# Modular_RFPA_v105.net
KiCad netlist of a schematic drawn in EAGLE
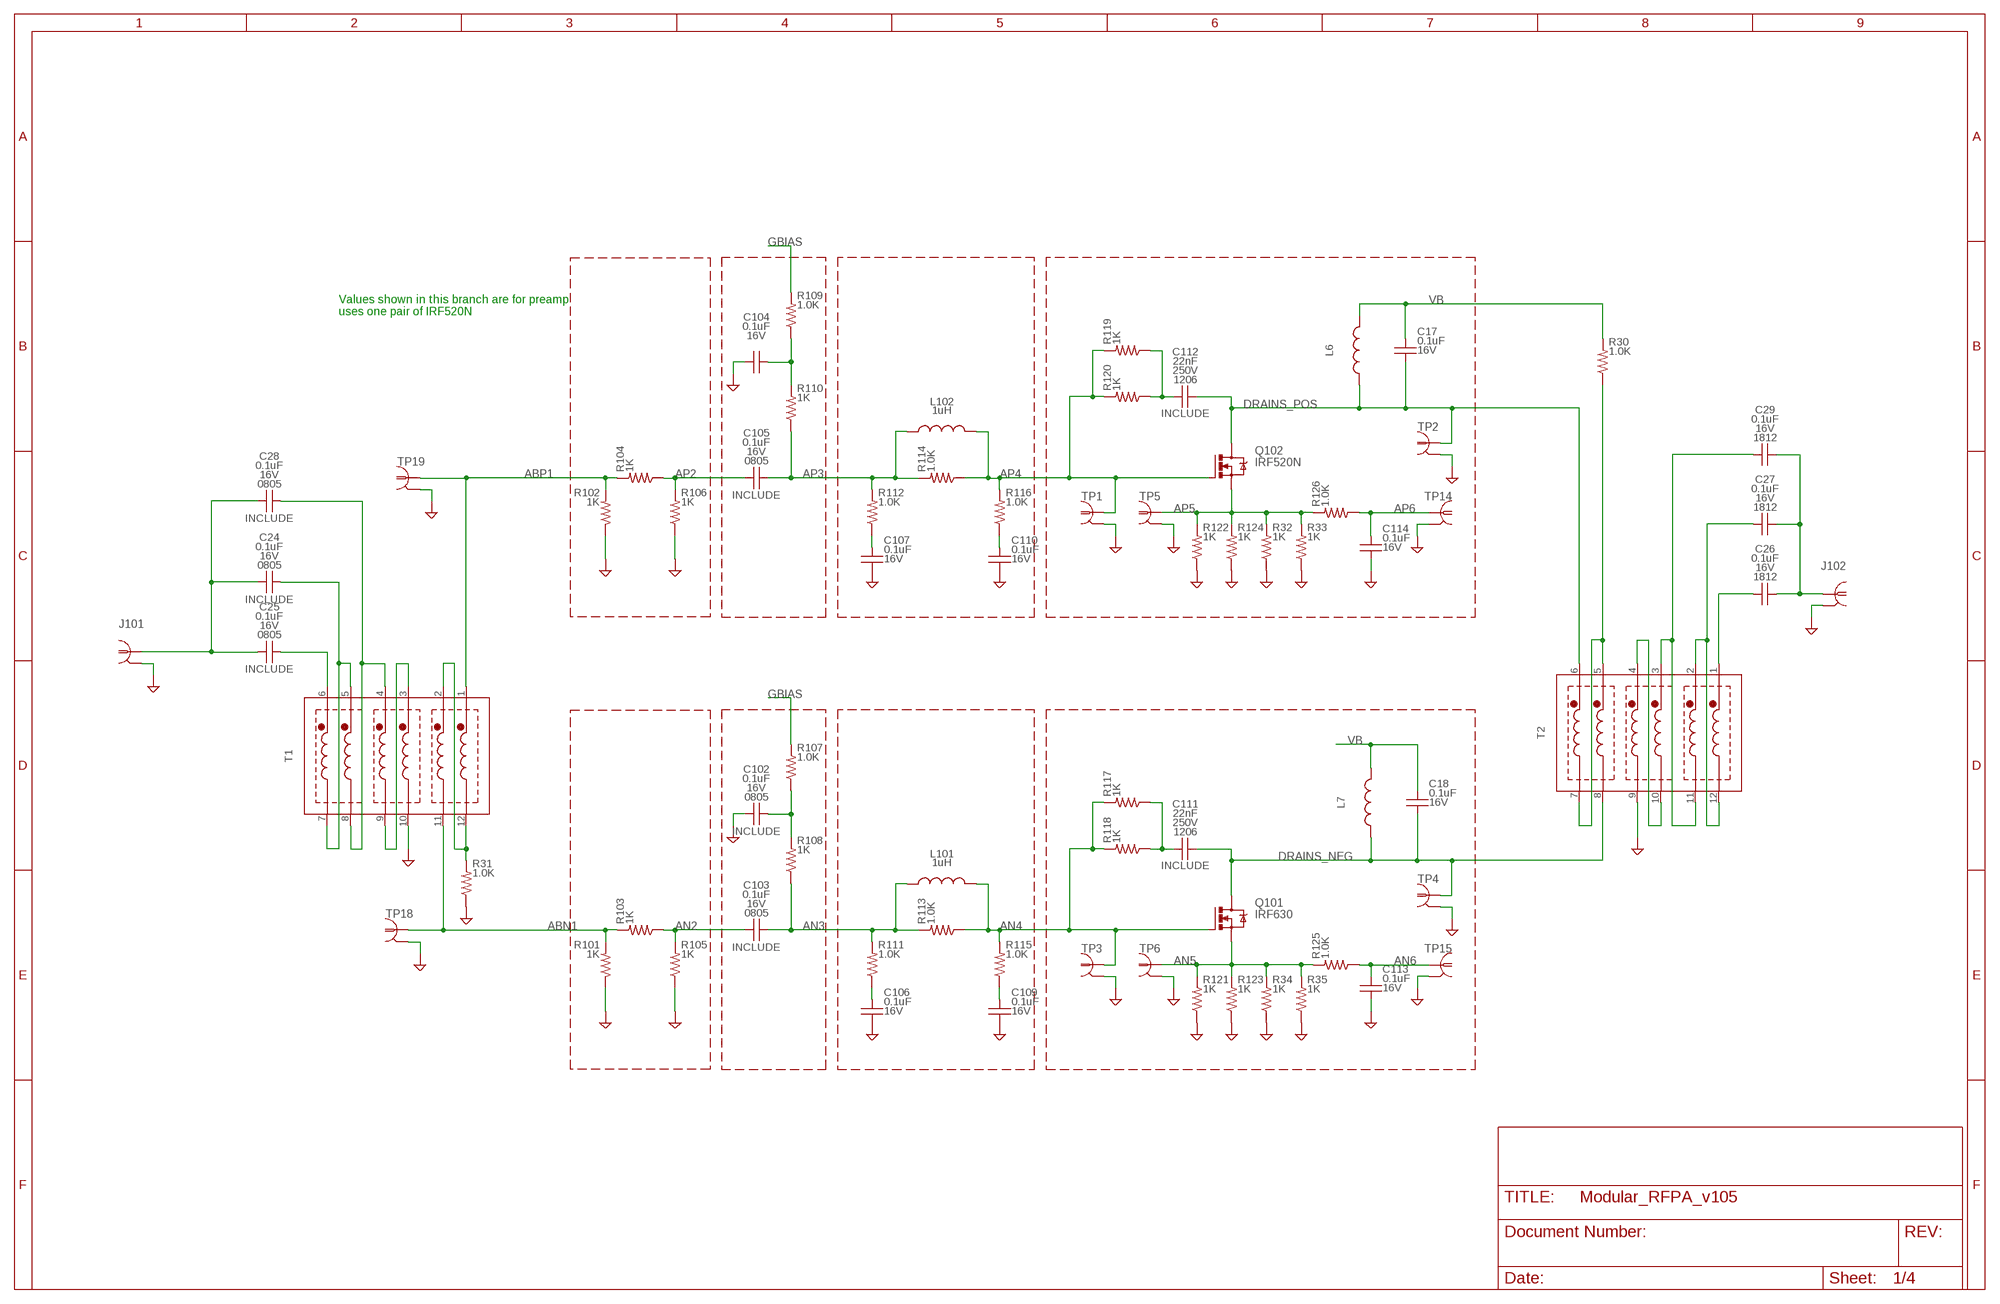
[diagram p0: schematic, sheet 1, part 1 of 2]
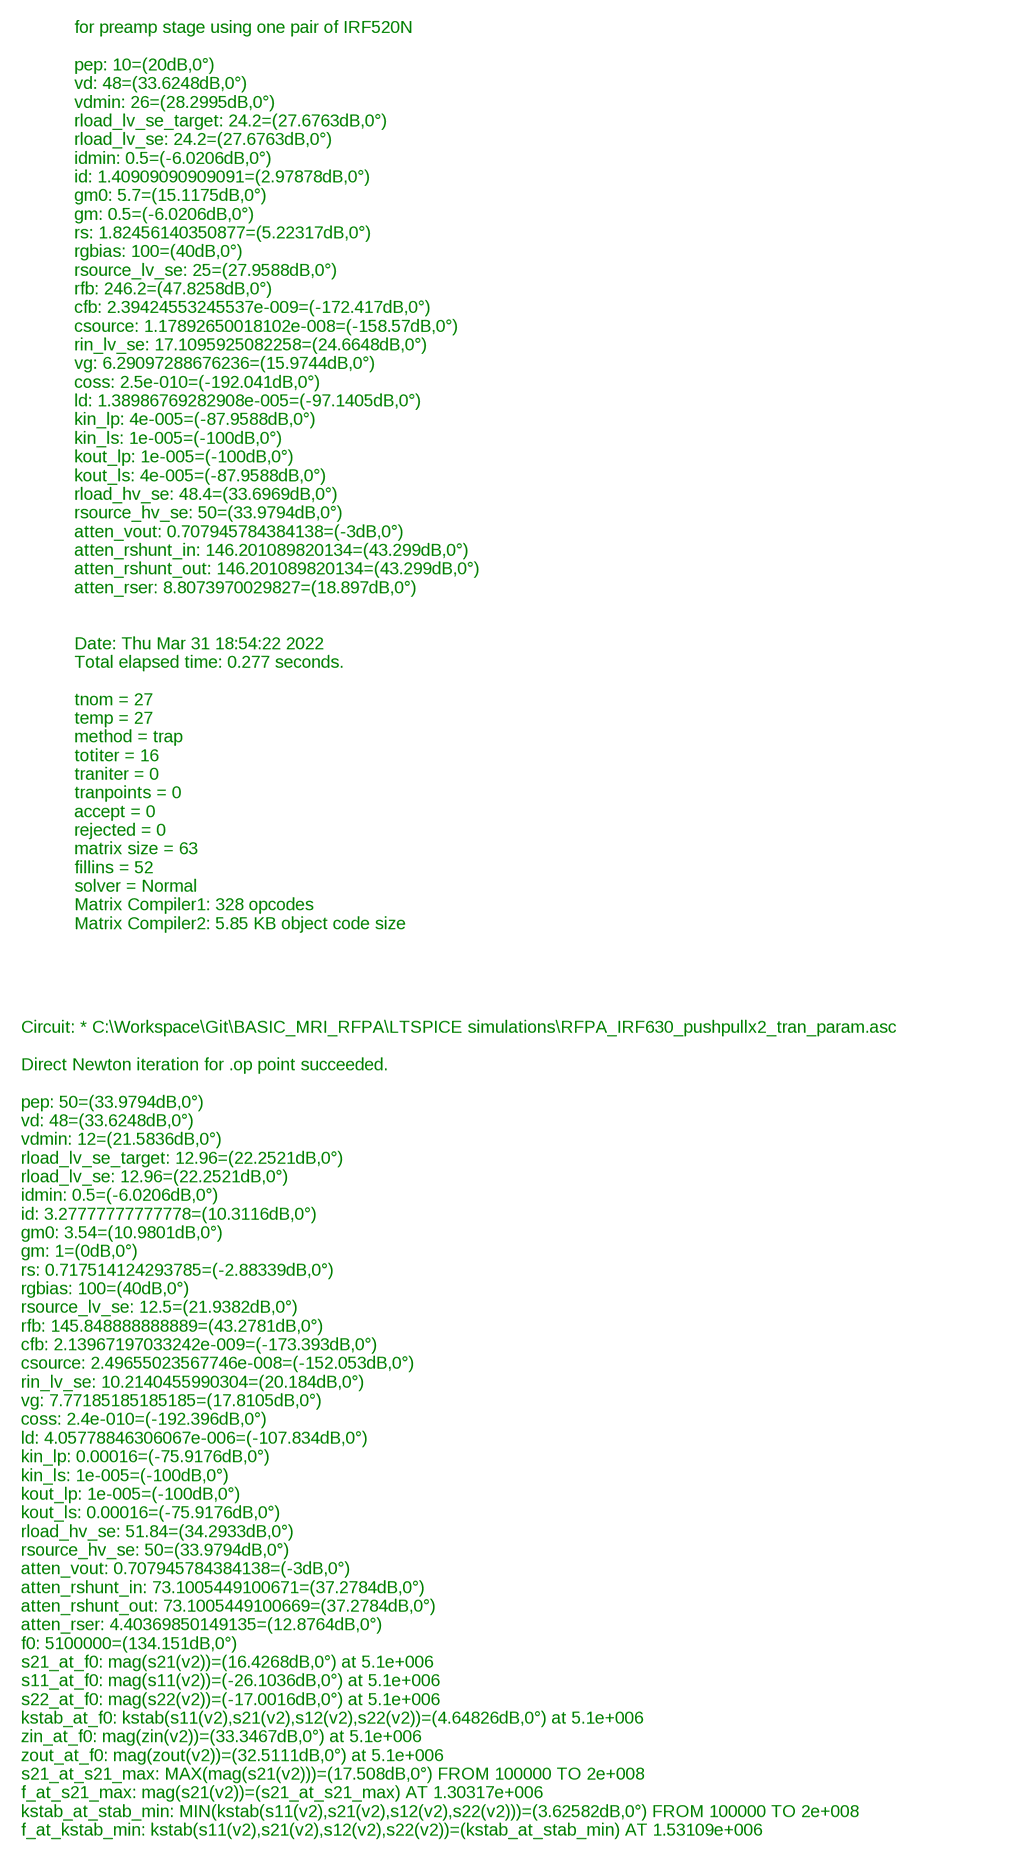
[diagram p1: schematic, sheet 1, part 2 of 2]
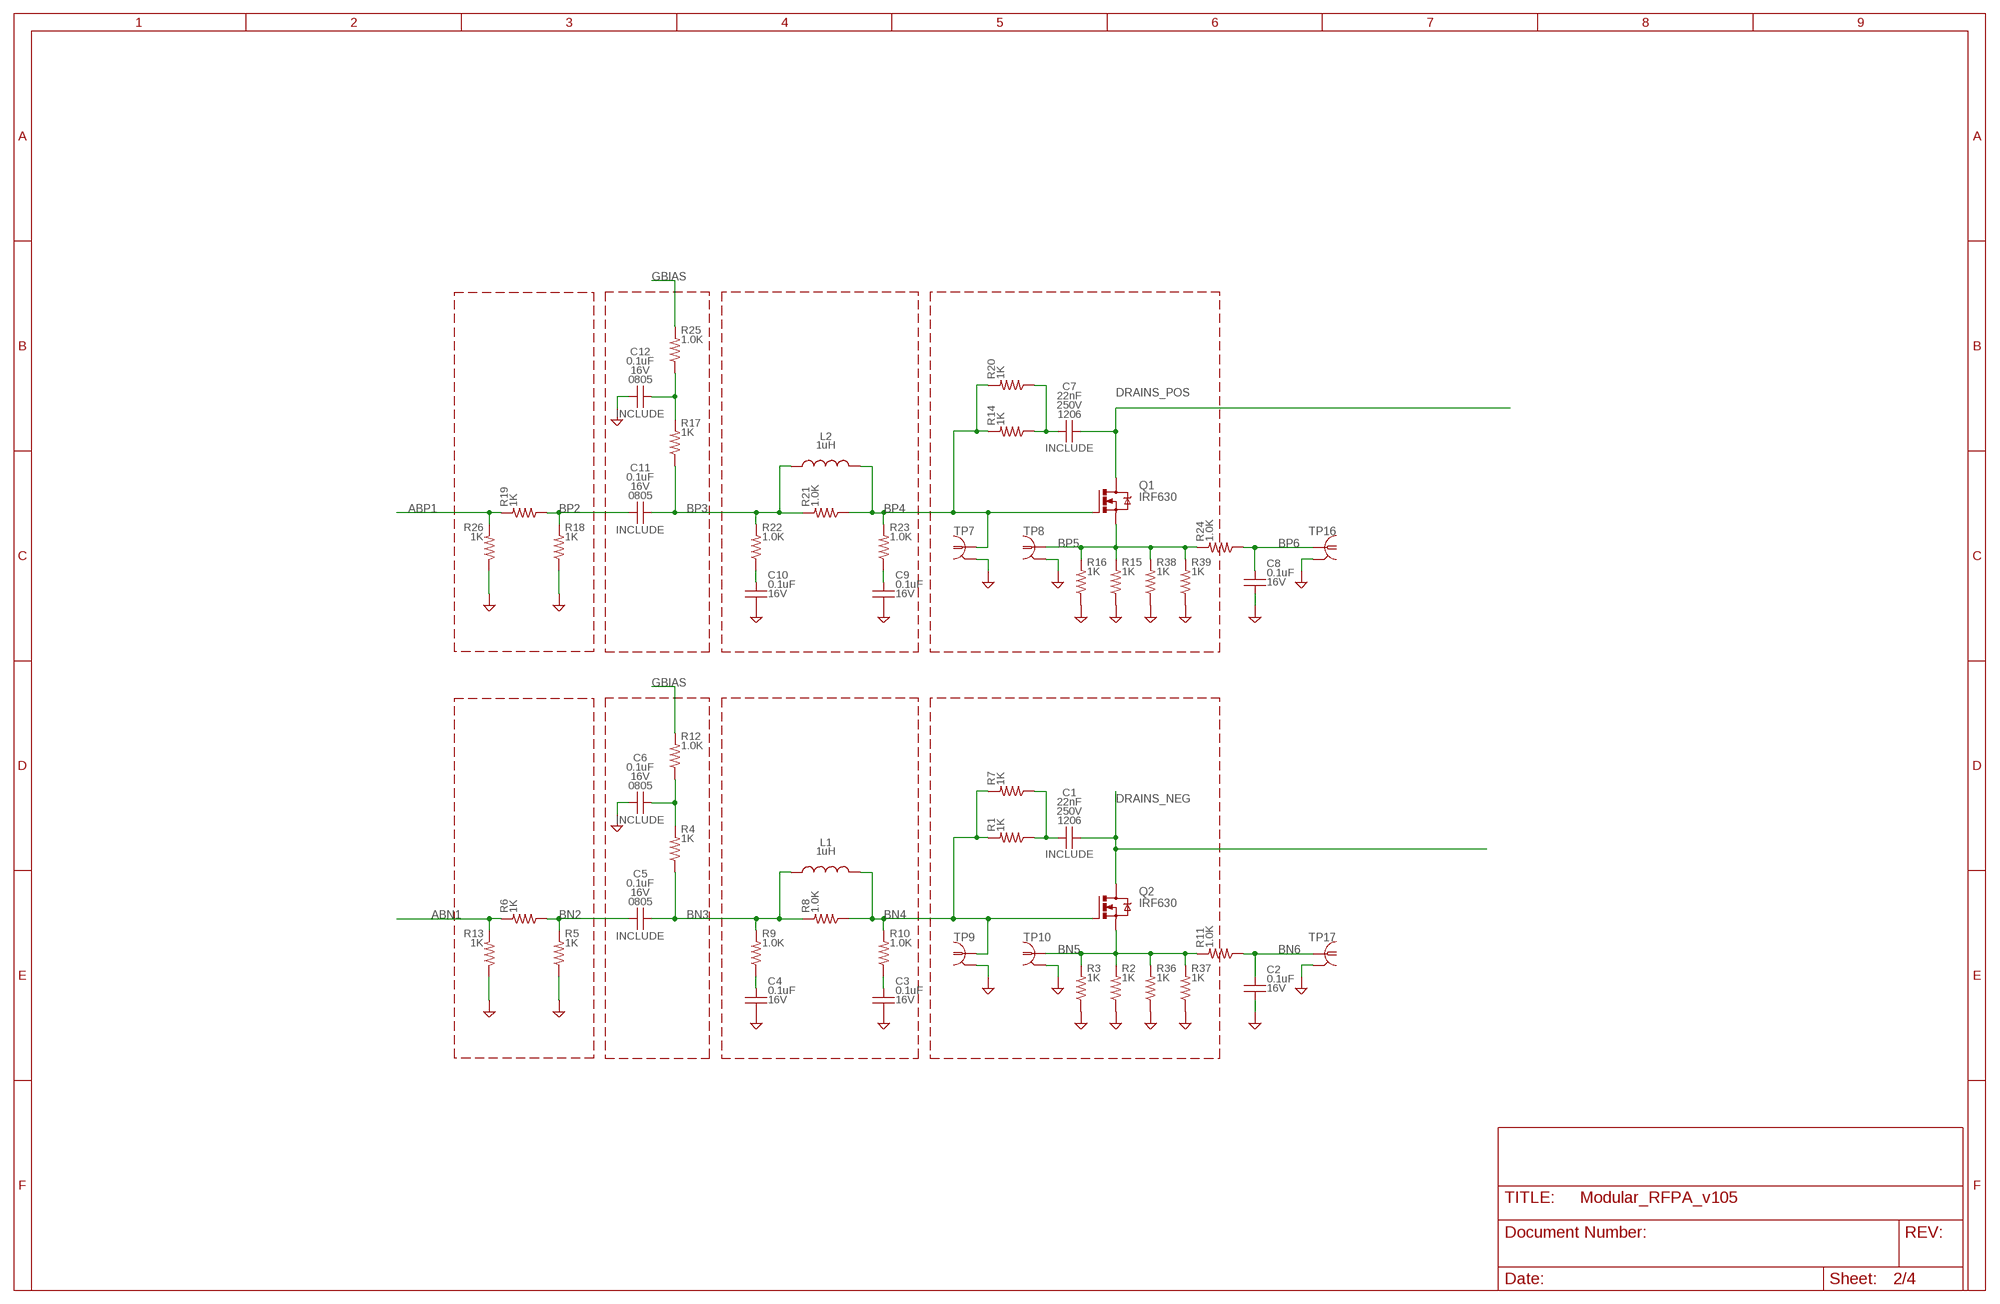
[diagram p2: schematic, sheet 2]
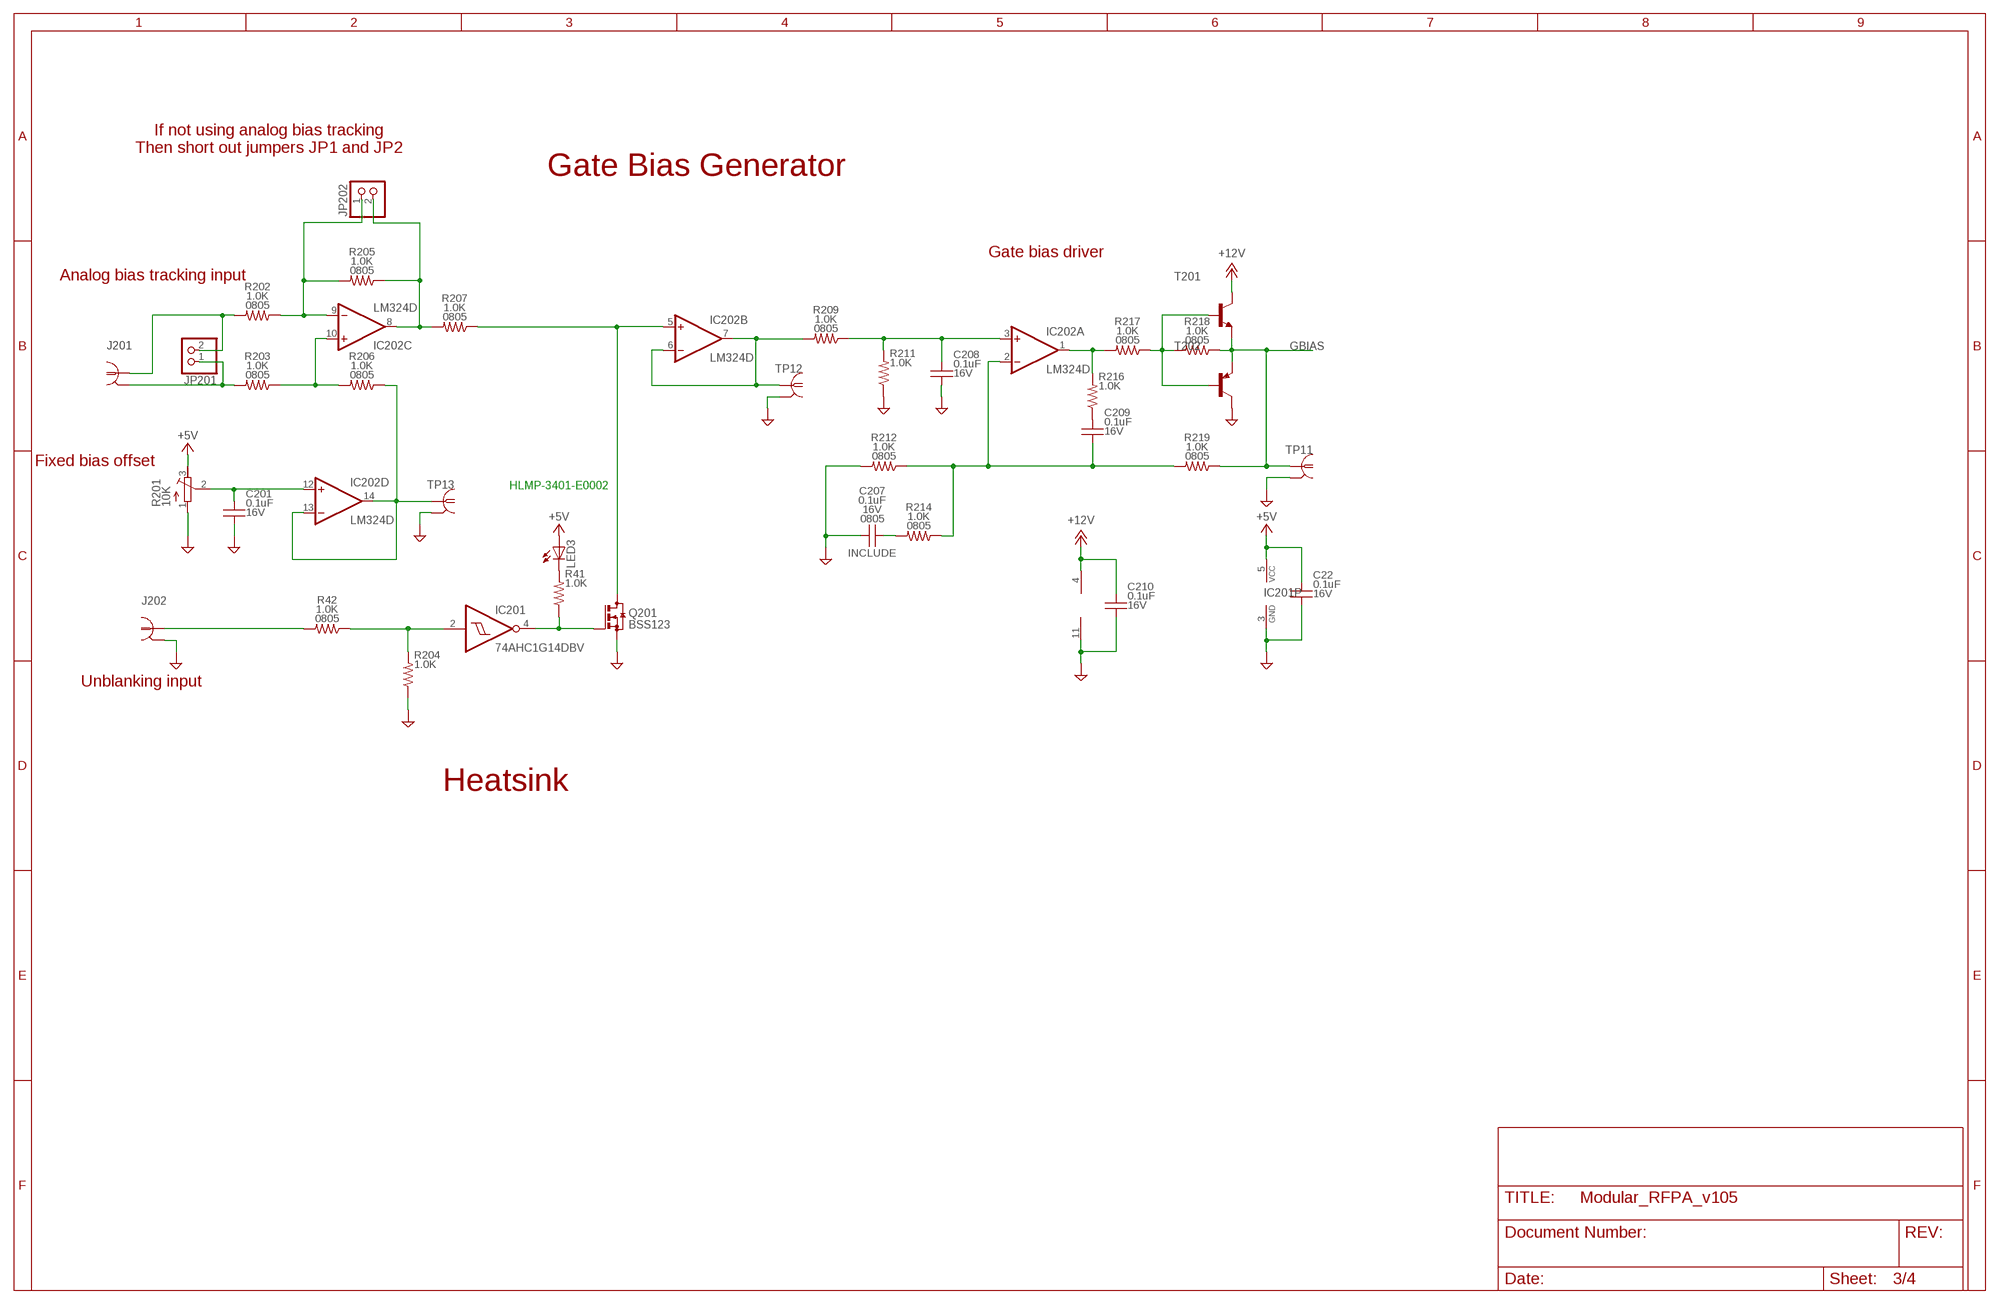
[diagram p3: schematic, sheet 3]
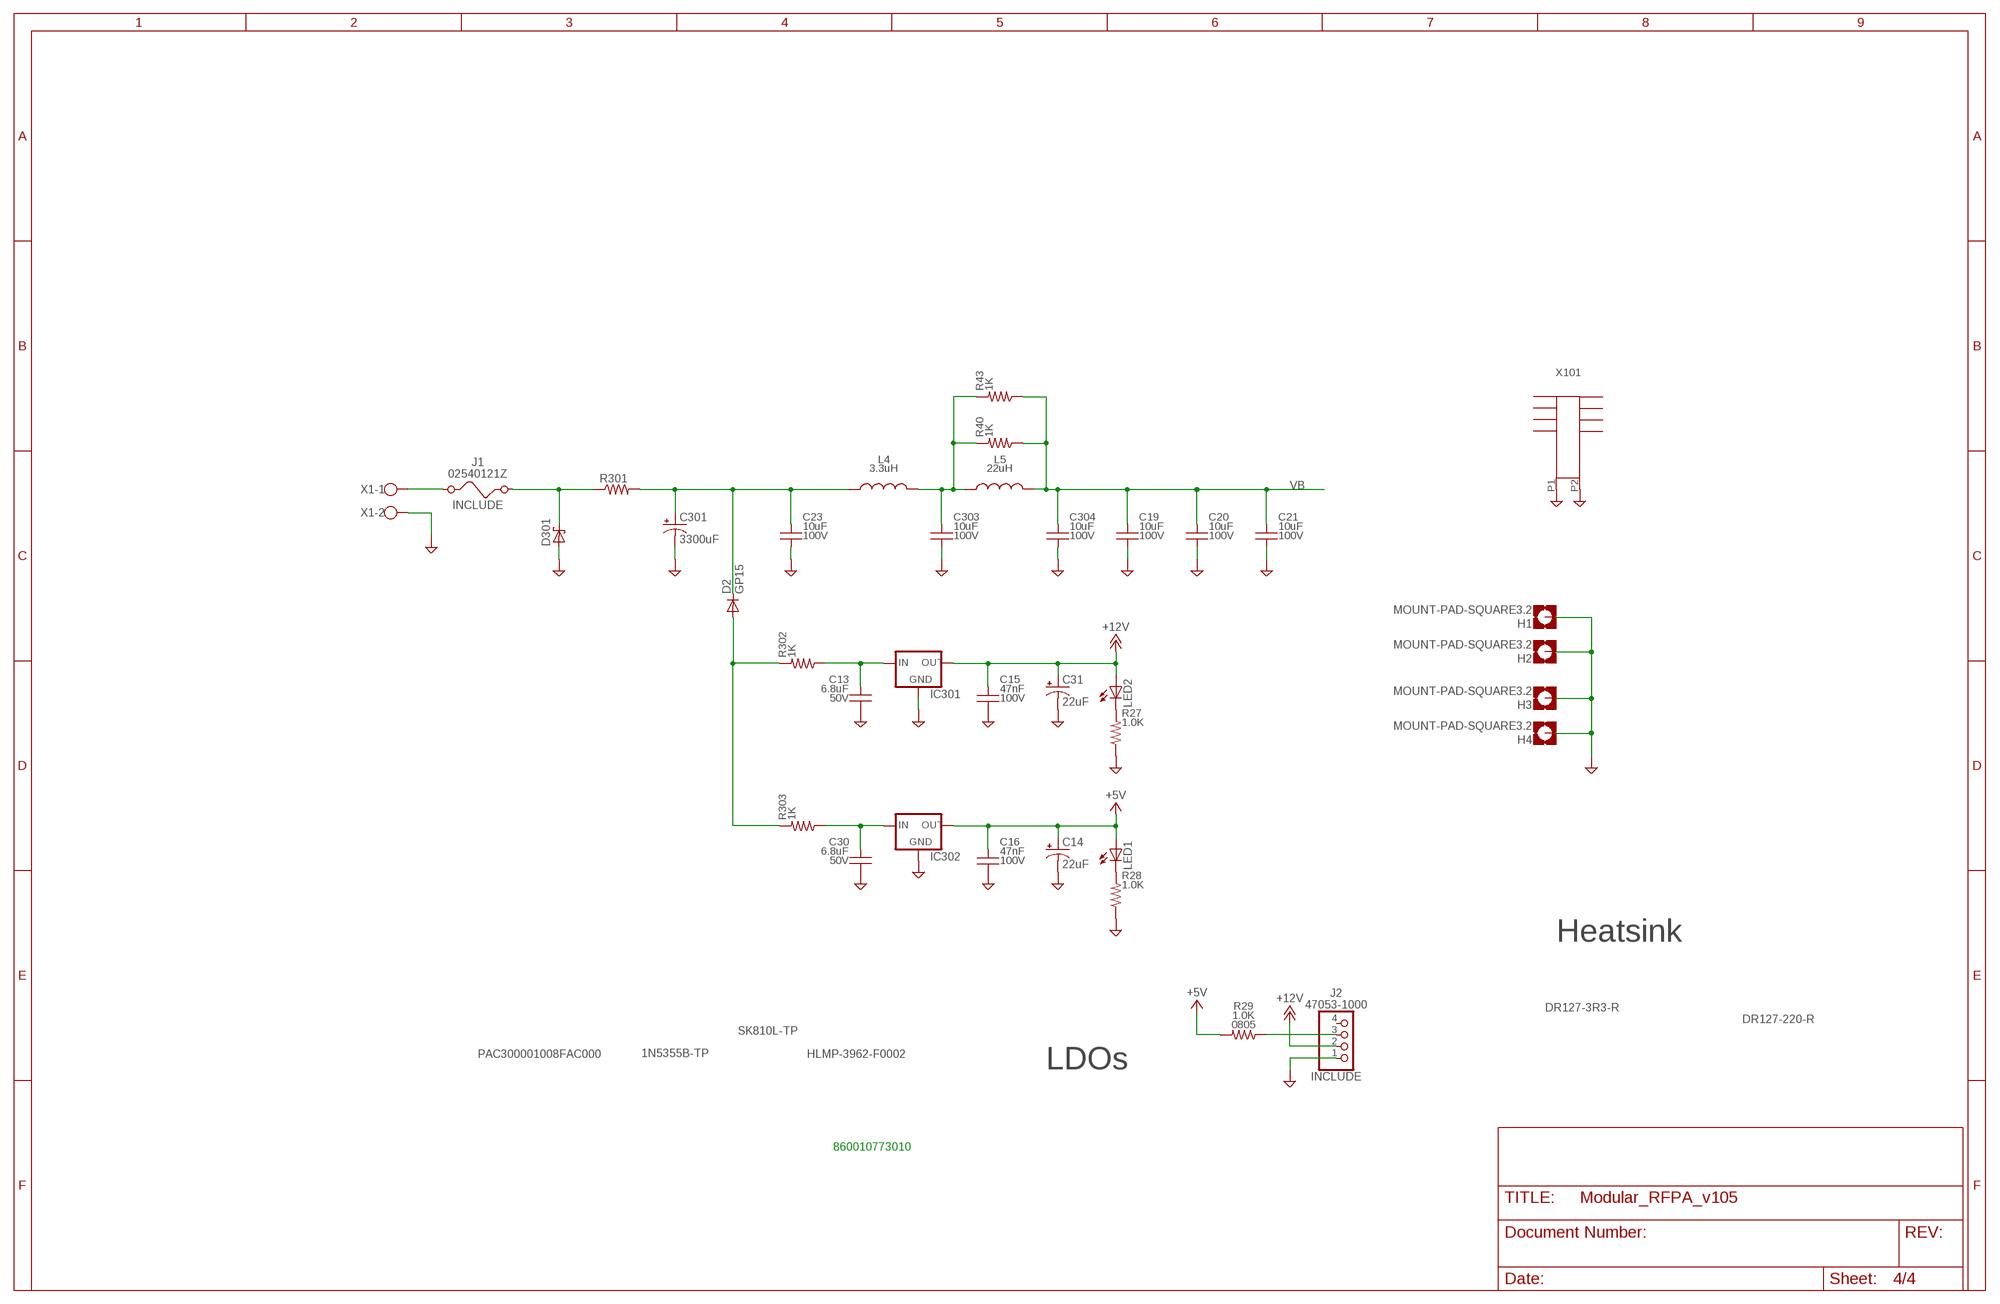
[diagram p4: schematic, sheet 4]

(export (version "E")
  (design (tool "Eeschema 10.0.6"))
  (components
    (comp (ref "C17")
      (value "0.1uF")
      (footprint "eagle-import:C1812")
      (fields (field (name "VOLTAGE") "16V"))
      (libsource (lib "eagle-import") (part "CC1812"))
    )
    (comp (ref "C18")
      (value "0.1uF")
      (footprint "eagle-import:C1812")
      (fields (field (name "VOLTAGE") "16V"))
      (libsource (lib "eagle-import") (part "CC1812"))
    )
    (comp (ref "C24")
      (value "0.1uF")
      (footprint "eagle-import:0805_IPC-7351B")
      (fields (field (name "PACKAGE") "0805") (field (name "VOLTAGE") "16V") (field (name "BOM") "INCLUDE"))
      (libsource (lib "eagle-import") (part "C0805_IPCC-0.1U-16V-0805-X7R"))
    )
    (comp (ref "C25")
      (value "0.1uF")
      (footprint "eagle-import:0805_IPC-7351B")
      (fields (field (name "PACKAGE") "0805") (field (name "VOLTAGE") "16V") (field (name "BOM") "INCLUDE"))
      (libsource (lib "eagle-import") (part "C0805_IPCC-0.1U-16V-0805-X7R"))
    )
    (comp (ref "C26")
      (value "0.1uF")
      (footprint "eagle-import:C1812")
      (fields (field (name "VOLTAGE") "16V") (field (name "PACKAGE") "1812"))
      (libsource (lib "eagle-import") (part "CC1812"))
    )
    (comp (ref "C27")
      (value "0.1uF")
      (footprint "eagle-import:C1812")
      (fields (field (name "VOLTAGE") "16V") (field (name "PACKAGE") "1812"))
      (libsource (lib "eagle-import") (part "CC1812"))
    )
    (comp (ref "C28")
      (value "0.1uF")
      (footprint "eagle-import:0805_IPC-7351B")
      (fields (field (name "PACKAGE") "0805") (field (name "VOLTAGE") "16V") (field (name "BOM") "INCLUDE"))
      (libsource (lib "eagle-import") (part "C0805_IPCC-0.1U-16V-0805-X7R"))
    )
    (comp (ref "C29")
      (value "0.1uF")
      (footprint "eagle-import:C1812")
      (fields (field (name "VOLTAGE") "16V") (field (name "PACKAGE") "1812"))
      (libsource (lib "eagle-import") (part "CC1812"))
    )
    (comp (ref "C102")
      (value "0.1uF")
      (footprint "eagle-import:0805_IPC-7351B")
      (fields (field (name "PACKAGE") "0805") (field (name "VOLTAGE") "16V") (field (name "BOM") "INCLUDE"))
      (libsource (lib "eagle-import") (part "C0805_IPCC-0.1U-16V-0805-X7R"))
    )
    (comp (ref "C103")
      (value "0.1uF")
      (footprint "eagle-import:0805_IPC-7351B")
      (fields (field (name "PACKAGE") "0805") (field (name "VOLTAGE") "16V") (field (name "BOM") "INCLUDE"))
      (libsource (lib "eagle-import") (part "C0805_IPCC-0.1U-16V-0805-X7R"))
    )
    (comp (ref "C104")
      (value "0.1uF")
      (footprint "eagle-import:0805_IPC-7351B")
      (fields (field (name "PACKAGE") "0805") (field (name "VOLTAGE") "16V") (field (name "BOM") "INCLUDE"))
      (libsource (lib "eagle-import") (part "C0805_IPCC-0.1U-16V-0805-X7R"))
    )
    (comp (ref "C105")
      (value "0.1uF")
      (footprint "eagle-import:0805_IPC-7351B")
      (fields (field (name "PACKAGE") "0805") (field (name "VOLTAGE") "16V") (field (name "BOM") "INCLUDE"))
      (libsource (lib "eagle-import") (part "C0805_IPCC-0.1U-16V-0805-X7R"))
    )
    (comp (ref "C106")
      (value "0.1uF")
      (footprint "eagle-import:0805_IPC-7351B")
      (fields (field (name "VOLTAGE") "16V"))
      (libsource (lib "eagle-import") (part "C0805_IPCC-0.1U-16V-0805-X7R"))
    )
    (comp (ref "C107")
      (value "0.1uF")
      (footprint "eagle-import:0805_IPC-7351B")
      (fields (field (name "VOLTAGE") "16V"))
      (libsource (lib "eagle-import") (part "C0805_IPCC-0.1U-16V-0805-X7R"))
    )
    (comp (ref "C109")
      (value "0.1uF")
      (footprint "eagle-import:0805_IPC-7351B")
      (fields (field (name "VOLTAGE") "16V"))
      (libsource (lib "eagle-import") (part "C0805_IPCC-0.1U-16V-0805-X7R"))
    )
    (comp (ref "C110")
      (value "0.1uF")
      (footprint "eagle-import:0805_IPC-7351B")
      (fields (field (name "VOLTAGE") "16V"))
      (libsource (lib "eagle-import") (part "C0805_IPCC-0.1U-16V-0805-X7R"))
    )
    (comp (ref "C111")
      (value "22nF")
      (footprint "eagle-import:C1206")
      (fields
        (field (name "BOM") "INCLUDE")
        (field (name "PACKAGE") "1206")
        (field (name "PARTNO") "C3216NP02E223J160AA")
        (field (name "VOLTAGE") "250V")
      )
      (libsource (lib "eagle-import") (part "CC1206C-22N-250V-5%-1206-NP0"))
    )
    (comp (ref "C112")
      (value "22nF")
      (footprint "eagle-import:C1206")
      (fields
        (field (name "BOM") "INCLUDE")
        (field (name "PACKAGE") "1206")
        (field (name "PARTNO") "C3216NP02E223J160AA")
        (field (name "VOLTAGE") "250V")
      )
      (libsource (lib "eagle-import") (part "CC1206C-22N-250V-5%-1206-NP0"))
    )
    (comp (ref "C113")
      (value "0.1uF")
      (footprint "eagle-import:0805_IPC-7351B")
      (fields (field (name "VOLTAGE") "16V"))
      (libsource (lib "eagle-import") (part "C0805_IPCC-0.1U-16V-0805-X7R"))
    )
    (comp (ref "C114")
      (value "0.1uF")
      (footprint "eagle-import:0805_IPC-7351B")
      (fields (field (name "VOLTAGE") "16V"))
      (libsource (lib "eagle-import") (part "C0805_IPCC-0.1U-16V-0805-X7R"))
    )
    (comp (ref "J101")
      (value "COAXBNC_EDGE")
      (footprint "eagle-import:BNC_EDGE")
      (libsource (lib "eagle-import") (part "COAXBNC_EDGE"))
    )
    (comp (ref "J102")
      (value "COAXBNC_EDGE")
      (footprint "eagle-import:BNC_EDGE")
      (libsource (lib "eagle-import") (part "COAXBNC_EDGE"))
    )
    (comp (ref "L6") (value "L") (footprint "eagle-import:DR127") (libsource (lib "eagle-import") (part "L")))
    (comp (ref "L7") (value "L") (footprint "eagle-import:DR127") (libsource (lib "eagle-import") (part "L")))
    (comp (ref "L101")
      (value "1uH")
      (footprint "eagle-import:L1008")
      (fields (field (name "PARTNO") "1008CS-102XJEC"))
      (libsource (lib "eagle-import") (part "L_CHIP1008L-1.0U-AIR-5%-1008-0.37A"))
    )
    (comp (ref "L102")
      (value "1uH")
      (footprint "eagle-import:L1008")
      (fields (field (name "PARTNO") "1008CS-102XJEC"))
      (libsource (lib "eagle-import") (part "L_CHIP1008L-1.0U-AIR-5%-1008-0.37A"))
    )
    (comp (ref "Q101")
      (value "IRF630")
      (footprint "eagle-import:TO220BV")
      (libsource (lib "eagle-import") (part "IRF540"))
    )
    (comp (ref "Q102")
      (value "IRF520N")
      (footprint "eagle-import:TO220BV")
      (libsource (lib "eagle-import") (part "IRF540"))
    )
    (comp (ref "R30")
      (value "1.0K")
      (footprint "eagle-import:0805_IPC-7351B")
      (libsource (lib "eagle-import") (part "R0805_IPCR-1.0K-0.1%-0805-0.1W"))
    )
    (comp (ref "R31")
      (value "1.0K")
      (footprint "eagle-import:0805_IPC-7351B")
      (libsource (lib "eagle-import") (part "R0805_IPCR-1.0K-0.1%-0805-0.1W"))
    )
    (comp (ref "R32")
      (value "1K")
      (footprint "eagle-import:R2512")
      (fields (field (name "POWER") "1"))
      (libsource (lib "eagle-import") (part "RR2512R-1K-1%-2512-1W"))
    )
    (comp (ref "R33")
      (value "1K")
      (footprint "eagle-import:R2512")
      (fields (field (name "POWER") "1"))
      (libsource (lib "eagle-import") (part "RR2512R-1K-1%-2512-1W"))
    )
    (comp (ref "R34")
      (value "1K")
      (footprint "eagle-import:R2512")
      (fields (field (name "POWER") "1"))
      (libsource (lib "eagle-import") (part "RR2512R-1K-1%-2512-1W"))
    )
    (comp (ref "R35")
      (value "1K")
      (footprint "eagle-import:R2512")
      (fields (field (name "POWER") "1"))
      (libsource (lib "eagle-import") (part "RR2512R-1K-1%-2512-1W"))
    )
    (comp (ref "R101")
      (value "1K")
      (footprint "eagle-import:R1206")
      (fields (field (name "POWER") "0.25"))
      (libsource (lib "eagle-import") (part "RR1206R-1.0K-1%-1206-0.25W"))
    )
    (comp (ref "R102")
      (value "1K")
      (footprint "eagle-import:R1206")
      (fields (field (name "POWER") "0.25"))
      (libsource (lib "eagle-import") (part "RR1206R-1.0K-1%-1206-0.25W"))
    )
    (comp (ref "R103")
      (value "1K")
      (footprint "eagle-import:R1206")
      (fields (field (name "POWER") "0.25"))
      (libsource (lib "eagle-import") (part "RR1206R-1.0K-1%-1206-0.25W"))
    )
    (comp (ref "R104")
      (value "1K")
      (footprint "eagle-import:R1206")
      (fields (field (name "POWER") "0.25"))
      (libsource (lib "eagle-import") (part "RR1206R-1.0K-1%-1206-0.25W"))
    )
    (comp (ref "R105")
      (value "1K")
      (footprint "eagle-import:R1206")
      (fields (field (name "POWER") "0.25"))
      (libsource (lib "eagle-import") (part "RR1206R-1.0K-1%-1206-0.25W"))
    )
    (comp (ref "R106")
      (value "1K")
      (footprint "eagle-import:R1206")
      (fields (field (name "POWER") "0.25"))
      (libsource (lib "eagle-import") (part "RR1206R-1.0K-1%-1206-0.25W"))
    )
    (comp (ref "R107")
      (value "1.0K")
      (footprint "eagle-import:0805_IPC-7351B")
      (libsource (lib "eagle-import") (part "R0805_IPCR-1.0K-0.1%-0805-0.1W"))
    )
    (comp (ref "R108")
      (value "1K")
      (footprint "eagle-import:R1206")
      (fields (field (name "POWER") "0.25"))
      (libsource (lib "eagle-import") (part "RR1206R-1.0K-1%-1206-0.25W"))
    )
    (comp (ref "R109")
      (value "1.0K")
      (footprint "eagle-import:0805_IPC-7351B")
      (libsource (lib "eagle-import") (part "R0805_IPCR-1.0K-0.1%-0805-0.1W"))
    )
    (comp (ref "R110")
      (value "1K")
      (footprint "eagle-import:R1206")
      (fields (field (name "POWER") "0.25"))
      (libsource (lib "eagle-import") (part "RR1206R-1.0K-1%-1206-0.25W"))
    )
    (comp (ref "R111")
      (value "1.0K")
      (footprint "eagle-import:0805_IPC-7351B")
      (libsource (lib "eagle-import") (part "R0805_IPCR-1.0K-0.1%-0805-0.1W"))
    )
    (comp (ref "R112")
      (value "1.0K")
      (footprint "eagle-import:0805_IPC-7351B")
      (libsource (lib "eagle-import") (part "R0805_IPCR-1.0K-0.1%-0805-0.1W"))
    )
    (comp (ref "R113")
      (value "1.0K")
      (footprint "eagle-import:0805_IPC-7351B")
      (libsource (lib "eagle-import") (part "R0805_IPCR-1.0K-0.1%-0805-0.1W"))
    )
    (comp (ref "R114")
      (value "1.0K")
      (footprint "eagle-import:0805_IPC-7351B")
      (libsource (lib "eagle-import") (part "R0805_IPCR-1.0K-0.1%-0805-0.1W"))
    )
    (comp (ref "R115")
      (value "1.0K")
      (footprint "eagle-import:0805_IPC-7351B")
      (libsource (lib "eagle-import") (part "R0805_IPCR-1.0K-0.1%-0805-0.1W"))
    )
    (comp (ref "R116")
      (value "1.0K")
      (footprint "eagle-import:0805_IPC-7351B")
      (libsource (lib "eagle-import") (part "R0805_IPCR-1.0K-0.1%-0805-0.1W"))
    )
    (comp (ref "R117")
      (value "1K")
      (footprint "eagle-import:R2512")
      (fields (field (name "POWER") "1"))
      (libsource (lib "eagle-import") (part "RR2512R-1K-1%-2512-1W"))
    )
    (comp (ref "R118")
      (value "1K")
      (footprint "eagle-import:R2512")
      (fields (field (name "POWER") "1"))
      (libsource (lib "eagle-import") (part "RR2512R-1K-1%-2512-1W"))
    )
    (comp (ref "R119")
      (value "1K")
      (footprint "eagle-import:R2512")
      (fields (field (name "POWER") "1"))
      (libsource (lib "eagle-import") (part "RR2512R-1K-1%-2512-1W"))
    )
    (comp (ref "R120")
      (value "1K")
      (footprint "eagle-import:R2512")
      (fields (field (name "POWER") "1"))
      (libsource (lib "eagle-import") (part "RR2512R-1K-1%-2512-1W"))
    )
    (comp (ref "R121")
      (value "1K")
      (footprint "eagle-import:R2512")
      (fields (field (name "POWER") "1"))
      (libsource (lib "eagle-import") (part "RR2512R-1K-1%-2512-1W"))
    )
    (comp (ref "R122")
      (value "1K")
      (footprint "eagle-import:R2512")
      (fields (field (name "POWER") "1"))
      (libsource (lib "eagle-import") (part "RR2512R-1K-1%-2512-1W"))
    )
    (comp (ref "R123")
      (value "1K")
      (footprint "eagle-import:R2512")
      (fields (field (name "POWER") "1"))
      (libsource (lib "eagle-import") (part "RR2512R-1K-1%-2512-1W"))
    )
    (comp (ref "R124")
      (value "1K")
      (footprint "eagle-import:R2512")
      (fields (field (name "POWER") "1"))
      (libsource (lib "eagle-import") (part "RR2512R-1K-1%-2512-1W"))
    )
    (comp (ref "R125")
      (value "1.0K")
      (footprint "eagle-import:0805_IPC-7351B")
      (libsource (lib "eagle-import") (part "R0805_IPCR-1.0K-0.1%-0805-0.1W"))
    )
    (comp (ref "R126")
      (value "1.0K")
      (footprint "eagle-import:0805_IPC-7351B")
      (fields (field (name "PACKAGE") "0805"))
      (libsource (lib "eagle-import") (part "R0805_IPCR-1.0K-0.1%-0805-0.1W"))
    )
    (comp (ref "T1")
      (value "HP4_TRAFO")
      (footprint "eagle-import:HP4")
      (libsource (lib "eagle-import") (part "HP4_TRAFO"))
    )
    (comp (ref "T2")
      (value "HP4_TRAFO")
      (footprint "eagle-import:HP4")
      (libsource (lib "eagle-import") (part "HP4_TRAFO"))
    )
    (comp (ref "TP1")
      (value "PROBE_TPTP_5MM")
      (footprint "eagle-import:PROBE_TP_5MM")
      (libsource (lib "eagle-import") (part "PROBE_TPTP_5MM"))
    )
    (comp (ref "TP2")
      (value "PROBE_TPTP_7P5MM")
      (footprint "eagle-import:PROBE_TP_7P5MM")
      (libsource (lib "eagle-import") (part "PROBE_TPTP_7P5MM"))
    )
    (comp (ref "TP3")
      (value "PROBE_TPTP_5MM")
      (footprint "eagle-import:PROBE_TP_5MM")
      (libsource (lib "eagle-import") (part "PROBE_TPTP_5MM"))
    )
    (comp (ref "TP4")
      (value "PROBE_TPTP_7P5MM")
      (footprint "eagle-import:PROBE_TP_7P5MM")
      (libsource (lib "eagle-import") (part "PROBE_TPTP_7P5MM"))
    )
    (comp (ref "TP5")
      (value "PROBE_TPTP_7P5MM")
      (footprint "eagle-import:PROBE_TP_7P5MM")
      (libsource (lib "eagle-import") (part "PROBE_TPTP_7P5MM"))
    )
    (comp (ref "TP6")
      (value "PROBE_TPTP_7P5MM")
      (footprint "eagle-import:PROBE_TP_7P5MM")
      (libsource (lib "eagle-import") (part "PROBE_TPTP_7P5MM"))
    )
    (comp (ref "TP14")
      (value "PROBE_TPTP_5MM")
      (footprint "eagle-import:PROBE_TP_5MM")
      (libsource (lib "eagle-import") (part "PROBE_TPTP_5MM"))
    )
    (comp (ref "TP15")
      (value "PROBE_TPTP_5MM")
      (footprint "eagle-import:PROBE_TP_5MM")
      (libsource (lib "eagle-import") (part "PROBE_TPTP_5MM"))
    )
    (comp (ref "TP18")
      (value "PROBE_TPTP_5MM")
      (footprint "eagle-import:PROBE_TP_5MM")
      (libsource (lib "eagle-import") (part "PROBE_TPTP_5MM"))
    )
    (comp (ref "TP19")
      (value "PROBE_TPTP_5MM")
      (footprint "eagle-import:PROBE_TP_5MM")
      (libsource (lib "eagle-import") (part "PROBE_TPTP_5MM"))
    )
    (comp (ref "C13")
      (value "6.8uF")
      (footprint "eagle-import:C1210")
      (fields (field (name "PARTNO") "CGA6P3X7S1H685K250AB") (field (name "VOLTAGE") "50V"))
      (libsource (lib "eagle-import") (part "CC1210CC-6.8U-50V-10%-1210-X7S"))
    )
    (comp (ref "C14")
      (value "22uF")
      (footprint "eagle-import:E2,5-7")
      (libsource (lib "eagle-import") (part "CPOL-USE2.5-7"))
    )
    (comp (ref "C15")
      (value "47nF")
      (footprint "eagle-import:C1206")
      (fields (field (name "PARTNO") "C3216C0G2A473J115AC") (field (name "VOLTAGE") "100V"))
      (libsource (lib "eagle-import") (part "CC1206C-47N-100V-5%-1206-NP0"))
    )
    (comp (ref "C16")
      (value "47nF")
      (footprint "eagle-import:C1206")
      (fields (field (name "PARTNO") "C3216C0G2A473J115AC") (field (name "VOLTAGE") "100V"))
      (libsource (lib "eagle-import") (part "CC1206C-47N-100V-5%-1206-NP0"))
    )
    (comp (ref "C19")
      (value "10uF")
      (footprint "eagle-import:C2220_CKG57N")
      (fields (field (name "PARTNO") "CGA9N3X7S2A106M230KE") (field (name "VOLTAGE") "100V"))
      (libsource (lib "eagle-import") (part "CC2220_CKG57NCC-10U-100V-20%-2220-X7T"))
    )
    (comp (ref "C20")
      (value "10uF")
      (footprint "eagle-import:C2220_CKG57N")
      (fields (field (name "PARTNO") "CGA9N3X7S2A106M230KE") (field (name "VOLTAGE") "100V"))
      (libsource (lib "eagle-import") (part "CC2220_CKG57NCC-10U-100V-20%-2220-X7T"))
    )
    (comp (ref "C21")
      (value "10uF")
      (footprint "eagle-import:C2220_CKG57N")
      (fields (field (name "PARTNO") "CGA9N3X7S2A106M230KE") (field (name "VOLTAGE") "100V"))
      (libsource (lib "eagle-import") (part "CC2220_CKG57NCC-10U-100V-20%-2220-X7T"))
    )
    (comp (ref "C23")
      (value "10uF")
      (footprint "eagle-import:C2220_CKG57N")
      (fields
        (field (name "BOM") "INCLUDE")
        (field (name "PACKAGE") "2220")
        (field (name "PARTNO") "CGA9N3X7S2A106M230KE")
        (field (name "VOLTAGE") "100V")
      )
      (libsource (lib "eagle-import") (part "CC2220_CKG57NCC-10U-100V-20%-2220-X7T"))
    )
    (comp (ref "C30")
      (value "6.8uF")
      (footprint "eagle-import:C1210")
      (fields (field (name "PARTNO") "CGA6P3X7S1H685K250AB") (field (name "VOLTAGE") "50V"))
      (libsource (lib "eagle-import") (part "CC1210CC-6.8U-50V-10%-1210-X7S"))
    )
    (comp (ref "C31")
      (value "22uF")
      (footprint "eagle-import:E2,5-7")
      (libsource (lib "eagle-import") (part "CPOL-USE2.5-7"))
    )
    (comp (ref "C301")
      (value "3300uF")
      (footprint "eagle-import:EB25D")
      (libsource (lib "eagle-import") (part "CPOL-USE10-25"))
    )
    (comp (ref "C303")
      (value "10uF")
      (footprint "eagle-import:C2220_CKG57N")
      (fields
        (field (name "BOM") "INCLUDE")
        (field (name "PACKAGE") "2220")
        (field (name "PARTNO") "CGA9N3X7S2A106M230KE")
        (field (name "VOLTAGE") "100V")
      )
      (libsource (lib "eagle-import") (part "CC2220_CKG57NCC-10U-100V-20%-2220-X7T"))
    )
    (comp (ref "C304")
      (value "10uF")
      (footprint "eagle-import:C2220_CKG57N")
      (fields (field (name "PARTNO") "CGA9N3X7S2A106M230KE") (field (name "VOLTAGE") "100V"))
      (libsource (lib "eagle-import") (part "CC2220_CKG57NCC-10U-100V-20%-2220-X7T"))
    )
    (comp (ref "D2")
      (value "GP15")
      (footprint "eagle-import:DO15-12")
      (libsource (lib "eagle-import") (part "GP15"))
    )
    (comp (ref "D301")
      (value "SCHOTTKY-DIODESMC")
      (footprint "eagle-import:SMC")
      (libsource (lib "eagle-import") (part "SCHOTTKY-DIODESMC"))
    )
    (comp (ref "H1")
      (value "MOUNT-PAD-SQUARE3.2")
      (footprint "eagle-import:3,2-PAD-SQUARE")
      (libsource (lib "eagle-import") (part "MOUNT-PAD-SQUARE3.2"))
    )
    (comp (ref "H2")
      (value "MOUNT-PAD-SQUARE3.2")
      (footprint "eagle-import:3,2-PAD-SQUARE")
      (libsource (lib "eagle-import") (part "MOUNT-PAD-SQUARE3.2"))
    )
    (comp (ref "H3")
      (value "MOUNT-PAD-SQUARE3.2")
      (footprint "eagle-import:3,2-PAD-SQUARE")
      (libsource (lib "eagle-import") (part "MOUNT-PAD-SQUARE3.2"))
    )
    (comp (ref "H4")
      (value "MOUNT-PAD-SQUARE3.2")
      (footprint "eagle-import:3,2-PAD-SQUARE")
      (libsource (lib "eagle-import") (part "MOUNT-PAD-SQUARE3.2"))
    )
    (comp (ref "IC301")
      (value "78XXS")
      (footprint "eagle-import:78XXS")
      (libsource (lib "eagle-import") (part "78XXS"))
    )
    (comp (ref "IC302")
      (value "78XXS")
      (footprint "eagle-import:78XXS")
      (libsource (lib "eagle-import") (part "78XXS"))
    )
    (comp (ref "J1")
      (value "FUSE_2P")
      (footprint "eagle-import:02540121Z")
      (fields (field (name "PARTNO") "02540121Z"))
      (libsource (lib "eagle-import") (part "FUSE_2P"))
    )
    (comp (ref "J2")
      (value "KK_PCFAN")
      (footprint "eagle-import:47053-1000")
      (fields (field (name "PARTNO") "47053-1000"))
      (libsource (lib "eagle-import") (part "KK_PCFAN"))
    )
    (comp (ref "L4")
      (value "3.3uH")
      (footprint "eagle-import:DR127")
      (libsource (lib "eagle-import") (part "L"))
    )
    (comp (ref "L5")
      (value "22uH")
      (footprint "eagle-import:DR127")
      (libsource (lib "eagle-import") (part "L"))
    )
    (comp (ref "LED1")
      (value "LED5MM")
      (footprint "eagle-import:LED5MM")
      (libsource (lib "eagle-import") (part "LED5MM"))
    )
    (comp (ref "LED2")
      (value "LED5MM")
      (footprint "eagle-import:LED5MM")
      (libsource (lib "eagle-import") (part "LED5MM"))
    )
    (comp (ref "R27")
      (value "1.0K")
      (footprint "eagle-import:0805_IPC-7351B")
      (libsource (lib "eagle-import") (part "R0805_IPCR-1.0K-0.1%-0805-0.1W"))
    )
    (comp (ref "R28")
      (value "1.0K")
      (footprint "eagle-import:0805_IPC-7351B")
      (libsource (lib "eagle-import") (part "R0805_IPCR-1.0K-0.1%-0805-0.1W"))
    )
    (comp (ref "R29")
      (value "1.0K")
      (footprint "eagle-import:0805_IPC-7351B")
      (fields (field (name "PACKAGE") "0805"))
      (libsource (lib "eagle-import") (part "R0805_IPCR-1.0K-0.1%-0805-0.1W"))
    )
    (comp (ref "R40")
      (value "1K")
      (footprint "eagle-import:R1206")
      (fields (field (name "POWER") "0.25"))
      (libsource (lib "eagle-import") (part "RR1206R-1.0K-1%-1206-0.25W"))
    )
    (comp (ref "R43")
      (value "1K")
      (footprint "eagle-import:R1206")
      (fields (field (name "POWER") "0.25"))
      (libsource (lib "eagle-import") (part "RR1206R-1.0K-1%-1206-0.25W"))
    )
    (comp (ref "R301")
      (value "R-US_0817/7V")
      (footprint "eagle-import:P0817V")
      (libsource (lib "eagle-import") (part "R-US_0817/7V"))
    )
    (comp (ref "R302")
      (value "1K")
      (footprint "eagle-import:R1206")
      (fields (field (name "POWER") "0.25"))
      (libsource (lib "eagle-import") (part "RR1206R-1.0K-1%-1206-0.25W"))
    )
    (comp (ref "R303")
      (value "1K")
      (footprint "eagle-import:R1206")
      (fields (field (name "POWER") "0.25"))
      (libsource (lib "eagle-import") (part "RR1206R-1.0K-1%-1206-0.25W"))
    )
    (comp (ref "X1")
      (value "W237-102")
      (footprint "eagle-import:W237-102")
      (fields (field (name "MPN") "237-102"))
      (libsource (lib "eagle-import") (part "W237-102"))
    )
    (comp (ref "X101")
      (value "HEATSINK_OMNI_DUAL30-75-D")
      (footprint "eagle-import:OMNI-UNI-30-75-D")
      (libsource (lib "eagle-import") (part "HEATSINK_OMNI_DUAL30-75-D"))
    )
    (comp (ref "C22")
      (value "0.1uF")
      (footprint "eagle-import:0805_IPC-7351B")
      (fields (field (name "VOLTAGE") "16V"))
      (libsource (lib "eagle-import") (part "C0805_IPCC-0.1U-16V-0805-X7R"))
    )
    (comp (ref "C201")
      (value "0.1uF")
      (footprint "eagle-import:0805_IPC-7351B")
      (fields (field (name "VOLTAGE") "16V"))
      (libsource (lib "eagle-import") (part "C0805_IPCC-0.1U-16V-0805-X7R"))
    )
    (comp (ref "C207")
      (value "0.1uF")
      (footprint "eagle-import:0805_IPC-7351B")
      (fields (field (name "PACKAGE") "0805") (field (name "VOLTAGE") "16V") (field (name "BOM") "INCLUDE"))
      (libsource (lib "eagle-import") (part "C0805_IPCC-0.1U-16V-0805-X7R"))
    )
    (comp (ref "C208")
      (value "0.1uF")
      (footprint "eagle-import:0805_IPC-7351B")
      (fields (field (name "VOLTAGE") "16V"))
      (libsource (lib "eagle-import") (part "C0805_IPCC-0.1U-16V-0805-X7R"))
    )
    (comp (ref "C209")
      (value "0.1uF")
      (footprint "eagle-import:0805_IPC-7351B")
      (fields (field (name "VOLTAGE") "16V"))
      (libsource (lib "eagle-import") (part "C0805_IPCC-0.1U-16V-0805-X7R"))
    )
    (comp (ref "C210")
      (value "0.1uF")
      (footprint "eagle-import:0805_IPC-7351B")
      (fields (field (name "VOLTAGE") "16V"))
      (libsource (lib "eagle-import") (part "C0805_IPCC-0.1U-16V-0805-X7R"))
    )
    (comp (ref "IC201")
      (value "74AHC1G14DBV")
      (footprint "eagle-import:SOT23-5")
      (libsource (lib "eagle-import") (part "741G14DBVAHC"))
    )
    (comp (ref "IC202")
      (value "LM324D")
      (footprint "eagle-import:SO14")
      (libsource (lib "eagle-import") (part "LM324D"))
    )
    (comp (ref "J201")
      (value "COAXBNC_EDGE")
      (footprint "eagle-import:BNC_EDGE")
      (libsource (lib "eagle-import") (part "COAXBNC_EDGE"))
    )
    (comp (ref "J202")
      (value "COAXBNC_EDGE")
      (footprint "eagle-import:BNC_EDGE")
      (libsource (lib "eagle-import") (part "COAXBNC_EDGE"))
    )
    (comp (ref "JP201")
      (value "PINHD-1X2")
      (footprint "eagle-import:1X02")
      (libsource (lib "eagle-import") (part "PINHD-1X2"))
    )
    (comp (ref "JP202")
      (value "PINHD-1X2")
      (footprint "eagle-import:1X02")
      (libsource (lib "eagle-import") (part "PINHD-1X2"))
    )
    (comp (ref "LED3")
      (value "LED5MM")
      (footprint "eagle-import:LED5MM")
      (libsource (lib "eagle-import") (part "LED5MM"))
    )
    (comp (ref "Q201")
      (value "BSS123")
      (footprint "eagle-import:SOT23")
      (libsource (lib "eagle-import") (part "BSS123"))
    )
    (comp (ref "R41")
      (value "1.0K")
      (footprint "eagle-import:0805_IPC-7351B")
      (libsource (lib "eagle-import") (part "R0805_IPCR-1.0K-0.1%-0805-0.1W"))
    )
    (comp (ref "R42")
      (value "1.0K")
      (footprint "eagle-import:0805_IPC-7351B")
      (fields (field (name "PACKAGE") "0805"))
      (libsource (lib "eagle-import") (part "R0805_IPCR-1.0K-0.1%-0805-0.1W"))
    )
    (comp (ref "R201")
      (value "10K")
      (footprint "eagle-import:RTRIM3299W")
      (libsource (lib "eagle-import") (part "R-TRIMM3299W"))
    )
    (comp (ref "R202")
      (value "1.0K")
      (footprint "eagle-import:0805_IPC-7351B")
      (fields (field (name "PACKAGE") "0805"))
      (libsource (lib "eagle-import") (part "R0805_IPCR-1.0K-0.1%-0805-0.1W"))
    )
    (comp (ref "R203")
      (value "1.0K")
      (footprint "eagle-import:0805_IPC-7351B")
      (fields (field (name "PACKAGE") "0805"))
      (libsource (lib "eagle-import") (part "R0805_IPCR-1.0K-0.1%-0805-0.1W"))
    )
    (comp (ref "R204")
      (value "1.0K")
      (footprint "eagle-import:0805_IPC-7351B")
      (libsource (lib "eagle-import") (part "R0805_IPCR-1.0K-0.1%-0805-0.1W"))
    )
    (comp (ref "R205")
      (value "1.0K")
      (footprint "eagle-import:0805_IPC-7351B")
      (fields (field (name "PACKAGE") "0805"))
      (libsource (lib "eagle-import") (part "R0805_IPCR-1.0K-0.1%-0805-0.1W"))
    )
    (comp (ref "R206")
      (value "1.0K")
      (footprint "eagle-import:0805_IPC-7351B")
      (fields (field (name "PACKAGE") "0805"))
      (libsource (lib "eagle-import") (part "R0805_IPCR-1.0K-0.1%-0805-0.1W"))
    )
    (comp (ref "R207")
      (value "1.0K")
      (footprint "eagle-import:0805_IPC-7351B")
      (fields (field (name "PACKAGE") "0805"))
      (libsource (lib "eagle-import") (part "R0805_IPCR-1.0K-0.1%-0805-0.1W"))
    )
    (comp (ref "R209")
      (value "1.0K")
      (footprint "eagle-import:0805_IPC-7351B")
      (fields (field (name "PACKAGE") "0805"))
      (libsource (lib "eagle-import") (part "R0805_IPCR-1.0K-0.1%-0805-0.1W"))
    )
    (comp (ref "R211")
      (value "1.0K")
      (footprint "eagle-import:0805_IPC-7351B")
      (libsource (lib "eagle-import") (part "R0805_IPCR-1.0K-0.1%-0805-0.1W"))
    )
    (comp (ref "R212")
      (value "1.0K")
      (footprint "eagle-import:0805_IPC-7351B")
      (fields (field (name "PACKAGE") "0805"))
      (libsource (lib "eagle-import") (part "R0805_IPCR-1.0K-0.1%-0805-0.1W"))
    )
    (comp (ref "R214")
      (value "1.0K")
      (footprint "eagle-import:0805_IPC-7351B")
      (fields (field (name "PACKAGE") "0805"))
      (libsource (lib "eagle-import") (part "R0805_IPCR-1.0K-0.1%-0805-0.1W"))
    )
    (comp (ref "R216")
      (value "1.0K")
      (footprint "eagle-import:0805_IPC-7351B")
      (libsource (lib "eagle-import") (part "R0805_IPCR-1.0K-0.1%-0805-0.1W"))
    )
    (comp (ref "R217")
      (value "1.0K")
      (footprint "eagle-import:0805_IPC-7351B")
      (fields (field (name "PACKAGE") "0805"))
      (libsource (lib "eagle-import") (part "R0805_IPCR-1.0K-0.1%-0805-0.1W"))
    )
    (comp (ref "R218")
      (value "1.0K")
      (footprint "eagle-import:0805_IPC-7351B")
      (fields (field (name "PACKAGE") "0805"))
      (libsource (lib "eagle-import") (part "R0805_IPCR-1.0K-0.1%-0805-0.1W"))
    )
    (comp (ref "R219")
      (value "1.0K")
      (footprint "eagle-import:0805_IPC-7351B")
      (fields (field (name "PACKAGE") "0805"))
      (libsource (lib "eagle-import") (part "R0805_IPCR-1.0K-0.1%-0805-0.1W"))
    )
    (comp (ref "T201")
      (value "BC808-NPN-SOT23-BEC")
      (footprint "eagle-import:SOT23-BEC")
      (libsource (lib "eagle-import") (part "-NPN-SOT23-BECBC808"))
    )
    (comp (ref "T202")
      (value "BC807-16-PNP-SOT23-BEC")
      (footprint "eagle-import:SOT23-BEC")
      (libsource (lib "eagle-import") (part "-PNP-SOT23-BECBC807-16"))
    )
    (comp (ref "TP11")
      (value "PROBE_TPTP_5MM")
      (footprint "eagle-import:PROBE_TP_5MM")
      (libsource (lib "eagle-import") (part "PROBE_TPTP_5MM"))
    )
    (comp (ref "TP12")
      (value "PROBE_TPTP_5MM")
      (footprint "eagle-import:PROBE_TP_5MM")
      (libsource (lib "eagle-import") (part "PROBE_TPTP_5MM"))
    )
    (comp (ref "TP13")
      (value "PROBE_TPTP_5MM")
      (footprint "eagle-import:PROBE_TP_5MM")
      (libsource (lib "eagle-import") (part "PROBE_TPTP_5MM"))
    )
    (comp (ref "C1")
      (value "22nF")
      (footprint "eagle-import:C1206")
      (fields
        (field (name "BOM") "INCLUDE")
        (field (name "PACKAGE") "1206")
        (field (name "PARTNO") "C3216NP02E223J160AA")
        (field (name "VOLTAGE") "250V")
      )
      (libsource (lib "eagle-import") (part "CC1206C-22N-250V-5%-1206-NP0"))
    )
    (comp (ref "C2")
      (value "0.1uF")
      (footprint "eagle-import:0805_IPC-7351B")
      (fields (field (name "VOLTAGE") "16V"))
      (libsource (lib "eagle-import") (part "C0805_IPCC-0.1U-16V-0805-X7R"))
    )
    (comp (ref "C3")
      (value "0.1uF")
      (footprint "eagle-import:0805_IPC-7351B")
      (fields (field (name "VOLTAGE") "16V"))
      (libsource (lib "eagle-import") (part "C0805_IPCC-0.1U-16V-0805-X7R"))
    )
    (comp (ref "C4")
      (value "0.1uF")
      (footprint "eagle-import:0805_IPC-7351B")
      (fields (field (name "VOLTAGE") "16V"))
      (libsource (lib "eagle-import") (part "C0805_IPCC-0.1U-16V-0805-X7R"))
    )
    (comp (ref "C5")
      (value "0.1uF")
      (footprint "eagle-import:0805_IPC-7351B")
      (fields (field (name "PACKAGE") "0805") (field (name "VOLTAGE") "16V") (field (name "BOM") "INCLUDE"))
      (libsource (lib "eagle-import") (part "C0805_IPCC-0.1U-16V-0805-X7R"))
    )
    (comp (ref "C6")
      (value "0.1uF")
      (footprint "eagle-import:0805_IPC-7351B")
      (fields (field (name "PACKAGE") "0805") (field (name "VOLTAGE") "16V") (field (name "BOM") "INCLUDE"))
      (libsource (lib "eagle-import") (part "C0805_IPCC-0.1U-16V-0805-X7R"))
    )
    (comp (ref "C7")
      (value "22nF")
      (footprint "eagle-import:C1206")
      (fields
        (field (name "BOM") "INCLUDE")
        (field (name "PACKAGE") "1206")
        (field (name "PARTNO") "C3216NP02E223J160AA")
        (field (name "VOLTAGE") "250V")
      )
      (libsource (lib "eagle-import") (part "CC1206C-22N-250V-5%-1206-NP0"))
    )
    (comp (ref "C8")
      (value "0.1uF")
      (footprint "eagle-import:0805_IPC-7351B")
      (fields (field (name "VOLTAGE") "16V"))
      (libsource (lib "eagle-import") (part "C0805_IPCC-0.1U-16V-0805-X7R"))
    )
    (comp (ref "C9")
      (value "0.1uF")
      (footprint "eagle-import:0805_IPC-7351B")
      (fields (field (name "VOLTAGE") "16V"))
      (libsource (lib "eagle-import") (part "C0805_IPCC-0.1U-16V-0805-X7R"))
    )
    (comp (ref "C10")
      (value "0.1uF")
      (footprint "eagle-import:0805_IPC-7351B")
      (fields (field (name "VOLTAGE") "16V"))
      (libsource (lib "eagle-import") (part "C0805_IPCC-0.1U-16V-0805-X7R"))
    )
    (comp (ref "C11")
      (value "0.1uF")
      (footprint "eagle-import:0805_IPC-7351B")
      (fields (field (name "PACKAGE") "0805") (field (name "VOLTAGE") "16V") (field (name "BOM") "INCLUDE"))
      (libsource (lib "eagle-import") (part "C0805_IPCC-0.1U-16V-0805-X7R"))
    )
    (comp (ref "C12")
      (value "0.1uF")
      (footprint "eagle-import:0805_IPC-7351B")
      (fields (field (name "PACKAGE") "0805") (field (name "VOLTAGE") "16V") (field (name "BOM") "INCLUDE"))
      (libsource (lib "eagle-import") (part "C0805_IPCC-0.1U-16V-0805-X7R"))
    )
    (comp (ref "L1")
      (value "1uH")
      (footprint "eagle-import:L1008")
      (fields (field (name "PARTNO") "1008CS-102XJEC"))
      (libsource (lib "eagle-import") (part "L_CHIP1008L-1.0U-AIR-5%-1008-0.37A"))
    )
    (comp (ref "L2")
      (value "1uH")
      (footprint "eagle-import:L1008")
      (fields (field (name "PARTNO") "1008CS-102XJEC"))
      (libsource (lib "eagle-import") (part "L_CHIP1008L-1.0U-AIR-5%-1008-0.37A"))
    )
    (comp (ref "Q1")
      (value "IRF630")
      (footprint "eagle-import:TO220BV")
      (libsource (lib "eagle-import") (part "IRF540"))
    )
    (comp (ref "Q2")
      (value "IRF630")
      (footprint "eagle-import:TO220BV")
      (libsource (lib "eagle-import") (part "IRF540"))
    )
    (comp (ref "R1")
      (value "1K")
      (footprint "eagle-import:R2512")
      (fields (field (name "POWER") "1"))
      (libsource (lib "eagle-import") (part "RR2512R-1K-1%-2512-1W"))
    )
    (comp (ref "R2")
      (value "1K")
      (footprint "eagle-import:R2512")
      (fields (field (name "POWER") "1"))
      (libsource (lib "eagle-import") (part "RR2512R-1K-1%-2512-1W"))
    )
    (comp (ref "R3")
      (value "1K")
      (footprint "eagle-import:R2512")
      (fields (field (name "POWER") "1"))
      (libsource (lib "eagle-import") (part "RR2512R-1K-1%-2512-1W"))
    )
    (comp (ref "R4")
      (value "1K")
      (footprint "eagle-import:R1206")
      (fields (field (name "POWER") "0.25"))
      (libsource (lib "eagle-import") (part "RR1206R-1.0K-1%-1206-0.25W"))
    )
    (comp (ref "R5")
      (value "1K")
      (footprint "eagle-import:R1206")
      (fields (field (name "POWER") "0.25"))
      (libsource (lib "eagle-import") (part "RR1206R-1.0K-1%-1206-0.25W"))
    )
    (comp (ref "R6")
      (value "1K")
      (footprint "eagle-import:R1206")
      (fields (field (name "POWER") "0.25"))
      (libsource (lib "eagle-import") (part "RR1206R-1.0K-1%-1206-0.25W"))
    )
    (comp (ref "R7")
      (value "1K")
      (footprint "eagle-import:R2512")
      (fields (field (name "POWER") "1"))
      (libsource (lib "eagle-import") (part "RR2512R-1K-1%-2512-1W"))
    )
    (comp (ref "R8")
      (value "1.0K")
      (footprint "eagle-import:0805_IPC-7351B")
      (libsource (lib "eagle-import") (part "R0805_IPCR-1.0K-0.1%-0805-0.1W"))
    )
    (comp (ref "R9")
      (value "1.0K")
      (footprint "eagle-import:0805_IPC-7351B")
      (libsource (lib "eagle-import") (part "R0805_IPCR-1.0K-0.1%-0805-0.1W"))
    )
    (comp (ref "R10")
      (value "1.0K")
      (footprint "eagle-import:0805_IPC-7351B")
      (libsource (lib "eagle-import") (part "R0805_IPCR-1.0K-0.1%-0805-0.1W"))
    )
    (comp (ref "R11")
      (value "1.0K")
      (footprint "eagle-import:0805_IPC-7351B")
      (libsource (lib "eagle-import") (part "R0805_IPCR-1.0K-0.1%-0805-0.1W"))
    )
    (comp (ref "R12")
      (value "1.0K")
      (footprint "eagle-import:0805_IPC-7351B")
      (libsource (lib "eagle-import") (part "R0805_IPCR-1.0K-0.1%-0805-0.1W"))
    )
    (comp (ref "R13")
      (value "1K")
      (footprint "eagle-import:R1206")
      (fields (field (name "POWER") "0.25"))
      (libsource (lib "eagle-import") (part "RR1206R-1.0K-1%-1206-0.25W"))
    )
    (comp (ref "R14")
      (value "1K")
      (footprint "eagle-import:R2512")
      (fields (field (name "POWER") "1"))
      (libsource (lib "eagle-import") (part "RR2512R-1K-1%-2512-1W"))
    )
    (comp (ref "R15")
      (value "1K")
      (footprint "eagle-import:R2512")
      (fields (field (name "POWER") "1"))
      (libsource (lib "eagle-import") (part "RR2512R-1K-1%-2512-1W"))
    )
    (comp (ref "R16")
      (value "1K")
      (footprint "eagle-import:R2512")
      (fields (field (name "POWER") "1"))
      (libsource (lib "eagle-import") (part "RR2512R-1K-1%-2512-1W"))
    )
    (comp (ref "R17")
      (value "1K")
      (footprint "eagle-import:R1206")
      (fields (field (name "POWER") "0.25"))
      (libsource (lib "eagle-import") (part "RR1206R-1.0K-1%-1206-0.25W"))
    )
    (comp (ref "R18")
      (value "1K")
      (footprint "eagle-import:R1206")
      (fields (field (name "POWER") "0.25"))
      (libsource (lib "eagle-import") (part "RR1206R-1.0K-1%-1206-0.25W"))
    )
    (comp (ref "R19")
      (value "1K")
      (footprint "eagle-import:R1206")
      (fields (field (name "POWER") "0.25"))
      (libsource (lib "eagle-import") (part "RR1206R-1.0K-1%-1206-0.25W"))
    )
    (comp (ref "R20")
      (value "1K")
      (footprint "eagle-import:R2512")
      (fields (field (name "POWER") "1"))
      (libsource (lib "eagle-import") (part "RR2512R-1K-1%-2512-1W"))
    )
    (comp (ref "R21")
      (value "1.0K")
      (footprint "eagle-import:0805_IPC-7351B")
      (libsource (lib "eagle-import") (part "R0805_IPCR-1.0K-0.1%-0805-0.1W"))
    )
    (comp (ref "R22")
      (value "1.0K")
      (footprint "eagle-import:0805_IPC-7351B")
      (libsource (lib "eagle-import") (part "R0805_IPCR-1.0K-0.1%-0805-0.1W"))
    )
    (comp (ref "R23")
      (value "1.0K")
      (footprint "eagle-import:0805_IPC-7351B")
      (libsource (lib "eagle-import") (part "R0805_IPCR-1.0K-0.1%-0805-0.1W"))
    )
    (comp (ref "R24")
      (value "1.0K")
      (footprint "eagle-import:0805_IPC-7351B")
      (libsource (lib "eagle-import") (part "R0805_IPCR-1.0K-0.1%-0805-0.1W"))
    )
    (comp (ref "R25")
      (value "1.0K")
      (footprint "eagle-import:0805_IPC-7351B")
      (libsource (lib "eagle-import") (part "R0805_IPCR-1.0K-0.1%-0805-0.1W"))
    )
    (comp (ref "R26")
      (value "1K")
      (footprint "eagle-import:R1206")
      (fields (field (name "POWER") "0.25"))
      (libsource (lib "eagle-import") (part "RR1206R-1.0K-1%-1206-0.25W"))
    )
    (comp (ref "R36")
      (value "1K")
      (footprint "eagle-import:R2512")
      (fields (field (name "POWER") "1"))
      (libsource (lib "eagle-import") (part "RR2512R-1K-1%-2512-1W"))
    )
    (comp (ref "R37")
      (value "1K")
      (footprint "eagle-import:R2512")
      (fields (field (name "POWER") "1"))
      (libsource (lib "eagle-import") (part "RR2512R-1K-1%-2512-1W"))
    )
    (comp (ref "R38")
      (value "1K")
      (footprint "eagle-import:R2512")
      (fields (field (name "POWER") "1"))
      (libsource (lib "eagle-import") (part "RR2512R-1K-1%-2512-1W"))
    )
    (comp (ref "R39")
      (value "1K")
      (footprint "eagle-import:R2512")
      (fields (field (name "POWER") "1"))
      (libsource (lib "eagle-import") (part "RR2512R-1K-1%-2512-1W"))
    )
    (comp (ref "TP7")
      (value "PROBE_TPTP_5MM")
      (footprint "eagle-import:PROBE_TP_5MM")
      (libsource (lib "eagle-import") (part "PROBE_TPTP_5MM"))
    )
    (comp (ref "TP8")
      (value "PROBE_TPTP_7P5MM")
      (footprint "eagle-import:PROBE_TP_7P5MM")
      (libsource (lib "eagle-import") (part "PROBE_TPTP_7P5MM"))
    )
    (comp (ref "TP9")
      (value "PROBE_TPTP_5MM")
      (footprint "eagle-import:PROBE_TP_5MM")
      (libsource (lib "eagle-import") (part "PROBE_TPTP_5MM"))
    )
    (comp (ref "TP10")
      (value "PROBE_TPTP_5MM")
      (footprint "eagle-import:PROBE_TP_5MM")
      (libsource (lib "eagle-import") (part "PROBE_TPTP_5MM"))
    )
    (comp (ref "TP16")
      (value "PROBE_TPTP_5MM")
      (footprint "eagle-import:PROBE_TP_5MM")
      (libsource (lib "eagle-import") (part "PROBE_TPTP_5MM"))
    )
    (comp (ref "TP17")
      (value "PROBE_TPTP_7P5MM")
      (footprint "eagle-import:PROBE_TP_7P5MM")
      (libsource (lib "eagle-import") (part "PROBE_TPTP_7P5MM"))
    )
  )
  (nets
    (net (code "1") (name "+5V") (class "Default")
      (node (ref "C14") (pin "+") (pinfunction "+_+") (pintype "passive"))
      (node (ref "C16") (pin "1") (pinfunction "1_1") (pintype "passive"))
      (node (ref "C22") (pin "1") (pinfunction "1_1") (pintype "passive"))
      (node (ref "IC201") (pin "5") (pinfunction "VCC_5") (pintype "power_in"))
      (node (ref "IC302") (pin "OUT") (pinfunction "OUT_OUT") (pintype "passive"))
      (node (ref "LED1") (pin "A") (pinfunction "A_A") (pintype "passive"))
      (node (ref "LED3") (pin "A") (pinfunction "A_A") (pintype "passive"))
      (node (ref "R201") (pin "3") (pinfunction "E_3") (pintype "passive"))
      (node (ref "R29") (pin "1") (pinfunction "1_1") (pintype "passive"))
    )
    (net (code "2") (name "+12V") (class "Default")
      (node (ref "C15") (pin "1") (pinfunction "1_1") (pintype "passive"))
      (node (ref "C210") (pin "1") (pinfunction "1_1") (pintype "passive"))
      (node (ref "C31") (pin "+") (pinfunction "+_+") (pintype "passive"))
      (node (ref "IC202") (pin "4") (pinfunction "V+_4") (pintype "power_in"))
      (node (ref "IC301") (pin "OUT") (pinfunction "OUT_OUT") (pintype "passive"))
      (node (ref "J2") (pin "2") (pinfunction "2_2") (pintype "passive"))
      (node (ref "LED2") (pin "A") (pinfunction "A_A") (pintype "passive"))
      (node (ref "T201") (pin "C") (pinfunction "C_C") (pintype "passive"))
    )
    (net (code "3") (name "ABN1") (class "Default")
      (node (ref "R101") (pin "1") (pinfunction "1_1") (pintype "passive"))
      (node (ref "R103") (pin "1") (pinfunction "1_1") (pintype "passive"))
      (node (ref "R13") (pin "1") (pinfunction "1_1") (pintype "passive"))
      (node (ref "R6") (pin "1") (pinfunction "1_1") (pintype "passive"))
      (node (ref "T1") (pin "11") (pinfunction "F2_11") (pintype "passive"))
      (node (ref "TP18") (pin "TP") (pinfunction "1_TP") (pintype "passive"))
    )
    (net (code "4") (name "ABP1") (class "Default")
      (node (ref "R102") (pin "1") (pinfunction "1_1") (pintype "passive"))
      (node (ref "R104") (pin "1") (pinfunction "1_1") (pintype "passive"))
      (node (ref "R19") (pin "1") (pinfunction "1_1") (pintype "passive"))
      (node (ref "R26") (pin "1") (pinfunction "1_1") (pintype "passive"))
      (node (ref "T1") (pin "1") (pinfunction "S1_1") (pintype "passive"))
      (node (ref "TP19") (pin "TP") (pinfunction "1_TP") (pintype "passive"))
    )
    (net (code "5") (name "AN2") (class "Default")
      (node (ref "C103") (pin "2") (pinfunction "2_2") (pintype "passive"))
      (node (ref "R103") (pin "2") (pinfunction "2_2") (pintype "passive"))
      (node (ref "R105") (pin "1") (pinfunction "1_1") (pintype "passive"))
    )
    (net (code "6") (name "AN3") (class "Default")
      (node (ref "C103") (pin "1") (pinfunction "1_1") (pintype "passive"))
      (node (ref "L101") (pin "1") (pinfunction "1_1") (pintype "passive"))
      (node (ref "R108") (pin "2") (pinfunction "2_2") (pintype "passive"))
      (node (ref "R111") (pin "1") (pinfunction "1_1") (pintype "passive"))
      (node (ref "R113") (pin "1") (pinfunction "1_1") (pintype "passive"))
    )
    (net (code "7") (name "AN4") (class "Default")
      (node (ref "L101") (pin "2") (pinfunction "2_2") (pintype "passive"))
      (node (ref "Q101") (pin "G") (pinfunction "G_G") (pintype "passive"))
      (node (ref "R113") (pin "2") (pinfunction "2_2") (pintype "passive"))
      (node (ref "R115") (pin "1") (pinfunction "1_1") (pintype "passive"))
      (node (ref "R117") (pin "1") (pinfunction "1_1") (pintype "passive"))
      (node (ref "R118") (pin "1") (pinfunction "1_1") (pintype "passive"))
      (node (ref "TP3") (pin "TP") (pinfunction "1_TP") (pintype "passive"))
    )
    (net (code "8") (name "AN5") (class "Default")
      (node (ref "Q101") (pin "S") (pinfunction "S_S") (pintype "passive"))
      (node (ref "R121") (pin "1") (pinfunction "1_1") (pintype "passive"))
      (node (ref "R123") (pin "1") (pinfunction "1_1") (pintype "passive"))
      (node (ref "R125") (pin "1") (pinfunction "1_1") (pintype "passive"))
      (node (ref "R34") (pin "1") (pinfunction "1_1") (pintype "passive"))
      (node (ref "R35") (pin "1") (pinfunction "1_1") (pintype "passive"))
      (node (ref "TP6") (pin "TP") (pinfunction "1_TP") (pintype "passive"))
    )
    (net (code "9") (name "AN6") (class "Default")
      (node (ref "C113") (pin "1") (pinfunction "1_1") (pintype "passive"))
      (node (ref "R125") (pin "2") (pinfunction "2_2") (pintype "passive"))
      (node (ref "TP15") (pin "TP") (pinfunction "1_TP") (pintype "passive"))
    )
    (net (code "10") (name "AP2") (class "Default")
      (node (ref "C105") (pin "2") (pinfunction "2_2") (pintype "passive"))
      (node (ref "R104") (pin "2") (pinfunction "2_2") (pintype "passive"))
      (node (ref "R106") (pin "1") (pinfunction "1_1") (pintype "passive"))
    )
    (net (code "11") (name "AP3") (class "Default")
      (node (ref "C105") (pin "1") (pinfunction "1_1") (pintype "passive"))
      (node (ref "L102") (pin "1") (pinfunction "1_1") (pintype "passive"))
      (node (ref "R110") (pin "2") (pinfunction "2_2") (pintype "passive"))
      (node (ref "R112") (pin "1") (pinfunction "1_1") (pintype "passive"))
      (node (ref "R114") (pin "1") (pinfunction "1_1") (pintype "passive"))
    )
    (net (code "12") (name "AP4") (class "Default")
      (node (ref "L102") (pin "2") (pinfunction "2_2") (pintype "passive"))
      (node (ref "Q102") (pin "G") (pinfunction "G_G") (pintype "passive"))
      (node (ref "R114") (pin "2") (pinfunction "2_2") (pintype "passive"))
      (node (ref "R116") (pin "1") (pinfunction "1_1") (pintype "passive"))
      (node (ref "R119") (pin "1") (pinfunction "1_1") (pintype "passive"))
      (node (ref "R120") (pin "1") (pinfunction "1_1") (pintype "passive"))
      (node (ref "TP1") (pin "TP") (pinfunction "1_TP") (pintype "passive"))
    )
    (net (code "13") (name "AP5") (class "Default")
      (node (ref "Q102") (pin "S") (pinfunction "S_S") (pintype "passive"))
      (node (ref "R122") (pin "1") (pinfunction "1_1") (pintype "passive"))
      (node (ref "R124") (pin "1") (pinfunction "1_1") (pintype "passive"))
      (node (ref "R126") (pin "1") (pinfunction "1_1") (pintype "passive"))
      (node (ref "R32") (pin "1") (pinfunction "1_1") (pintype "passive"))
      (node (ref "R33") (pin "1") (pinfunction "1_1") (pintype "passive"))
      (node (ref "TP5") (pin "TP") (pinfunction "1_TP") (pintype "passive"))
    )
    (net (code "14") (name "AP6") (class "Default")
      (node (ref "C114") (pin "1") (pinfunction "1_1") (pintype "passive"))
      (node (ref "R126") (pin "2") (pinfunction "2_2") (pintype "passive"))
      (node (ref "TP14") (pin "TP") (pinfunction "1_TP") (pintype "passive"))
    )
    (net (code "15") (name "BN2") (class "Default")
      (node (ref "C5") (pin "2") (pinfunction "2_2") (pintype "passive"))
      (node (ref "R5") (pin "1") (pinfunction "1_1") (pintype "passive"))
      (node (ref "R6") (pin "2") (pinfunction "2_2") (pintype "passive"))
    )
    (net (code "16") (name "BN3") (class "Default")
      (node (ref "C5") (pin "1") (pinfunction "1_1") (pintype "passive"))
      (node (ref "L1") (pin "1") (pinfunction "1_1") (pintype "passive"))
      (node (ref "R4") (pin "2") (pinfunction "2_2") (pintype "passive"))
      (node (ref "R8") (pin "1") (pinfunction "1_1") (pintype "passive"))
      (node (ref "R9") (pin "1") (pinfunction "1_1") (pintype "passive"))
    )
    (net (code "17") (name "BN4") (class "Default")
      (node (ref "L1") (pin "2") (pinfunction "2_2") (pintype "passive"))
      (node (ref "Q2") (pin "G") (pinfunction "G_G") (pintype "passive"))
      (node (ref "R1") (pin "1") (pinfunction "1_1") (pintype "passive"))
      (node (ref "R10") (pin "1") (pinfunction "1_1") (pintype "passive"))
      (node (ref "R7") (pin "1") (pinfunction "1_1") (pintype "passive"))
      (node (ref "R8") (pin "2") (pinfunction "2_2") (pintype "passive"))
      (node (ref "TP9") (pin "TP") (pinfunction "1_TP") (pintype "passive"))
    )
    (net (code "18") (name "BN5") (class "Default")
      (node (ref "Q2") (pin "S") (pinfunction "S_S") (pintype "passive"))
      (node (ref "R11") (pin "1") (pinfunction "1_1") (pintype "passive"))
      (node (ref "R2") (pin "1") (pinfunction "1_1") (pintype "passive"))
      (node (ref "R3") (pin "1") (pinfunction "1_1") (pintype "passive"))
      (node (ref "R36") (pin "1") (pinfunction "1_1") (pintype "passive"))
      (node (ref "R37") (pin "1") (pinfunction "1_1") (pintype "passive"))
      (node (ref "TP10") (pin "TP") (pinfunction "1_TP") (pintype "passive"))
    )
    (net (code "19") (name "BN6") (class "Default")
      (node (ref "C2") (pin "1") (pinfunction "1_1") (pintype "passive"))
      (node (ref "R11") (pin "2") (pinfunction "2_2") (pintype "passive"))
      (node (ref "TP17") (pin "TP") (pinfunction "1_TP") (pintype "passive"))
    )
    (net (code "20") (name "BP2") (class "Default")
      (node (ref "C11") (pin "2") (pinfunction "2_2") (pintype "passive"))
      (node (ref "R18") (pin "1") (pinfunction "1_1") (pintype "passive"))
      (node (ref "R19") (pin "2") (pinfunction "2_2") (pintype "passive"))
    )
    (net (code "21") (name "BP3") (class "Default")
      (node (ref "C11") (pin "1") (pinfunction "1_1") (pintype "passive"))
      (node (ref "L2") (pin "1") (pinfunction "1_1") (pintype "passive"))
      (node (ref "R17") (pin "2") (pinfunction "2_2") (pintype "passive"))
      (node (ref "R21") (pin "1") (pinfunction "1_1") (pintype "passive"))
      (node (ref "R22") (pin "1") (pinfunction "1_1") (pintype "passive"))
    )
    (net (code "22") (name "BP4") (class "Default")
      (node (ref "L2") (pin "2") (pinfunction "2_2") (pintype "passive"))
      (node (ref "Q1") (pin "G") (pinfunction "G_G") (pintype "passive"))
      (node (ref "R14") (pin "1") (pinfunction "1_1") (pintype "passive"))
      (node (ref "R20") (pin "1") (pinfunction "1_1") (pintype "passive"))
      (node (ref "R21") (pin "2") (pinfunction "2_2") (pintype "passive"))
      (node (ref "R23") (pin "1") (pinfunction "1_1") (pintype "passive"))
      (node (ref "TP7") (pin "TP") (pinfunction "1_TP") (pintype "passive"))
    )
    (net (code "23") (name "BP5") (class "Default")
      (node (ref "Q1") (pin "S") (pinfunction "S_S") (pintype "passive"))
      (node (ref "R15") (pin "1") (pinfunction "1_1") (pintype "passive"))
      (node (ref "R16") (pin "1") (pinfunction "1_1") (pintype "passive"))
      (node (ref "R24") (pin "1") (pinfunction "1_1") (pintype "passive"))
      (node (ref "R38") (pin "1") (pinfunction "1_1") (pintype "passive"))
      (node (ref "R39") (pin "1") (pinfunction "1_1") (pintype "passive"))
      (node (ref "TP8") (pin "TP") (pinfunction "1_TP") (pintype "passive"))
    )
    (net (code "24") (name "BP6") (class "Default")
      (node (ref "C8") (pin "1") (pinfunction "1_1") (pintype "passive"))
      (node (ref "R24") (pin "2") (pinfunction "2_2") (pintype "passive"))
      (node (ref "TP16") (pin "TP") (pinfunction "1_TP") (pintype "passive"))
    )
    (net (code "25") (name "DRAINS_NEG") (class "Default")
      (node (ref "C1") (pin "2") (pinfunction "2_2") (pintype "passive"))
      (node (ref "C111") (pin "2") (pinfunction "2_2") (pintype "passive"))
      (node (ref "C18") (pin "2") (pinfunction "2_2") (pintype "passive"))
      (node (ref "L7") (pin "1") (pinfunction "1_1") (pintype "passive"))
      (node (ref "Q101") (pin "D") (pinfunction "D_D") (pintype "passive"))
      (node (ref "Q2") (pin "D") (pinfunction "D_D") (pintype "passive"))
      (node (ref "T2") (pin "8") (pinfunction "F5_8") (pintype "passive"))
      (node (ref "TP4") (pin "TP") (pinfunction "1_TP") (pintype "passive"))
    )
    (net (code "26") (name "DRAINS_POS") (class "Default")
      (node (ref "C112") (pin "2") (pinfunction "2_2") (pintype "passive"))
      (node (ref "C17") (pin "2") (pinfunction "2_2") (pintype "passive"))
      (node (ref "C7") (pin "2") (pinfunction "2_2") (pintype "passive"))
      (node (ref "L6") (pin "1") (pinfunction "1_1") (pintype "passive"))
      (node (ref "Q1") (pin "D") (pinfunction "D_D") (pintype "passive"))
      (node (ref "Q102") (pin "D") (pinfunction "D_D") (pintype "passive"))
      (node (ref "T2") (pin "6") (pinfunction "S6_6") (pintype "passive"))
      (node (ref "TP2") (pin "TP") (pinfunction "1_TP") (pintype "passive"))
    )
    (net (code "27") (name "GBIAS") (class "Default")
      (node (ref "R107") (pin "1") (pinfunction "1_1") (pintype "passive"))
      (node (ref "R109") (pin "1") (pinfunction "1_1") (pintype "passive"))
      (node (ref "R12") (pin "1") (pinfunction "1_1") (pintype "passive"))
      (node (ref "R218") (pin "2") (pinfunction "2_2") (pintype "passive"))
      (node (ref "R219") (pin "2") (pinfunction "2_2") (pintype "passive"))
      (node (ref "R25") (pin "1") (pinfunction "1_1") (pintype "passive"))
      (node (ref "T201") (pin "E") (pinfunction "E_E") (pintype "passive"))
      (node (ref "T202") (pin "E") (pinfunction "E_E") (pintype "passive"))
      (node (ref "TP11") (pin "TP") (pinfunction "1_TP") (pintype "passive"))
    )
    (net (code "28") (name "GND") (class "Default")
      (node (ref "C10") (pin "2") (pinfunction "2_2") (pintype "passive"))
      (node (ref "C102") (pin "2") (pinfunction "2_2") (pintype "passive"))
      (node (ref "C104") (pin "2") (pinfunction "2_2") (pintype "passive"))
      (node (ref "C106") (pin "2") (pinfunction "2_2") (pintype "passive"))
      (node (ref "C107") (pin "2") (pinfunction "2_2") (pintype "passive"))
      (node (ref "C109") (pin "2") (pinfunction "2_2") (pintype "passive"))
      (node (ref "C110") (pin "2") (pinfunction "2_2") (pintype "passive"))
      (node (ref "C113") (pin "2") (pinfunction "2_2") (pintype "passive"))
      (node (ref "C114") (pin "2") (pinfunction "2_2") (pintype "passive"))
      (node (ref "C12") (pin "2") (pinfunction "2_2") (pintype "passive"))
      (node (ref "C13") (pin "2") (pinfunction "2_2") (pintype "passive"))
      (node (ref "C14") (pin "-") (pinfunction "-_-") (pintype "passive"))
      (node (ref "C15") (pin "2") (pinfunction "2_2") (pintype "passive"))
      (node (ref "C16") (pin "2") (pinfunction "2_2") (pintype "passive"))
      (node (ref "C19") (pin "2") (pinfunction "2_2") (pintype "passive"))
      (node (ref "C2") (pin "2") (pinfunction "2_2") (pintype "passive"))
      (node (ref "C20") (pin "2") (pinfunction "2_2") (pintype "passive"))
      (node (ref "C201") (pin "2") (pinfunction "2_2") (pintype "passive"))
      (node (ref "C207") (pin "2") (pinfunction "2_2") (pintype "passive"))
      (node (ref "C208") (pin "2") (pinfunction "2_2") (pintype "passive"))
      (node (ref "C21") (pin "2") (pinfunction "2_2") (pintype "passive"))
      (node (ref "C210") (pin "2") (pinfunction "2_2") (pintype "passive"))
      (node (ref "C22") (pin "2") (pinfunction "2_2") (pintype "passive"))
      (node (ref "C23") (pin "2") (pinfunction "2_2") (pintype "passive"))
      (node (ref "C3") (pin "2") (pinfunction "2_2") (pintype "passive"))
      (node (ref "C30") (pin "2") (pinfunction "2_2") (pintype "passive"))
      (node (ref "C301") (pin "-") (pinfunction "-_-") (pintype "passive"))
      (node (ref "C303") (pin "2") (pinfunction "2_2") (pintype "passive"))
      (node (ref "C304") (pin "2") (pinfunction "2_2") (pintype "passive"))
      (node (ref "C31") (pin "-") (pinfunction "-_-") (pintype "passive"))
      (node (ref "C4") (pin "2") (pinfunction "2_2") (pintype "passive"))
      (node (ref "C6") (pin "2") (pinfunction "2_2") (pintype "passive"))
      (node (ref "C8") (pin "2") (pinfunction "2_2") (pintype "passive"))
      (node (ref "C9") (pin "2") (pinfunction "2_2") (pintype "passive"))
      (node (ref "D301") (pin "A") (pinfunction "A_A") (pintype "passive"))
      (node (ref "H1") (pin "B3,2") (pinfunction "MOUNT_B3,2") (pintype "passive"))
      (node (ref "H2") (pin "B3,2") (pinfunction "MOUNT_B3,2") (pintype "passive"))
      (node (ref "H3") (pin "B3,2") (pinfunction "MOUNT_B3,2") (pintype "passive"))
      (node (ref "H4") (pin "B3,2") (pinfunction "MOUNT_B3,2") (pintype "passive"))
      (node (ref "IC201") (pin "3") (pinfunction "GND_3") (pintype "power_in"))
      (node (ref "IC202") (pin "11") (pinfunction "V-_11") (pintype "power_in"))
      (node (ref "IC301") (pin "GND") (pinfunction "GND_GND") (pintype "input"))
      (node (ref "IC302") (pin "GND") (pinfunction "GND_GND") (pintype "input"))
      (node (ref "J101") (pin "G1") (pinfunction "GND1_G1") (pintype "power_in"))
      (node (ref "J101") (pin "G2") (pinfunction "GND1_G2") (pintype "power_in"))
      (node (ref "J101") (pin "G3") (pinfunction "GND1_G3") (pintype "power_in"))
      (node (ref "J101") (pin "G4") (pinfunction "GND1_G4") (pintype "power_in"))
      (node (ref "J102") (pin "G1") (pinfunction "GND1_G1") (pintype "power_in"))
      (node (ref "J102") (pin "G2") (pinfunction "GND1_G2") (pintype "power_in"))
      (node (ref "J102") (pin "G3") (pinfunction "GND1_G3") (pintype "power_in"))
      (node (ref "J102") (pin "G4") (pinfunction "GND1_G4") (pintype "power_in"))
      (node (ref "J2") (pin "1") (pinfunction "1_1") (pintype "passive"))
      (node (ref "J202") (pin "G1") (pinfunction "GND1_G1") (pintype "power_in"))
      (node (ref "J202") (pin "G2") (pinfunction "GND1_G2") (pintype "power_in"))
      (node (ref "J202") (pin "G3") (pinfunction "GND1_G3") (pintype "power_in"))
      (node (ref "J202") (pin "G4") (pinfunction "GND1_G4") (pintype "power_in"))
      (node (ref "Q201") (pin "2") (pinfunction "S_2") (pintype "passive"))
      (node (ref "R101") (pin "2") (pinfunction "2_2") (pintype "passive"))
      (node (ref "R102") (pin "2") (pinfunction "2_2") (pintype "passive"))
      (node (ref "R105") (pin "2") (pinfunction "2_2") (pintype "passive"))
      (node (ref "R106") (pin "2") (pinfunction "2_2") (pintype "passive"))
      (node (ref "R121") (pin "2") (pinfunction "2_2") (pintype "passive"))
      (node (ref "R122") (pin "2") (pinfunction "2_2") (pintype "passive"))
      (node (ref "R123") (pin "2") (pinfunction "2_2") (pintype "passive"))
      (node (ref "R124") (pin "2") (pinfunction "2_2") (pintype "passive"))
      (node (ref "R13") (pin "2") (pinfunction "2_2") (pintype "passive"))
      (node (ref "R15") (pin "2") (pinfunction "2_2") (pintype "passive"))
      (node (ref "R16") (pin "2") (pinfunction "2_2") (pintype "passive"))
      (node (ref "R18") (pin "2") (pinfunction "2_2") (pintype "passive"))
      (node (ref "R2") (pin "2") (pinfunction "2_2") (pintype "passive"))
      (node (ref "R201") (pin "1") (pinfunction "A_1") (pintype "passive"))
      (node (ref "R204") (pin "2") (pinfunction "2_2") (pintype "passive"))
      (node (ref "R211") (pin "2") (pinfunction "2_2") (pintype "passive"))
      (node (ref "R212") (pin "1") (pinfunction "1_1") (pintype "passive"))
      (node (ref "R26") (pin "2") (pinfunction "2_2") (pintype "passive"))
      (node (ref "R27") (pin "2") (pinfunction "2_2") (pintype "passive"))
      (node (ref "R28") (pin "2") (pinfunction "2_2") (pintype "passive"))
      (node (ref "R3") (pin "2") (pinfunction "2_2") (pintype "passive"))
      (node (ref "R31") (pin "2") (pinfunction "2_2") (pintype "passive"))
      (node (ref "R32") (pin "2") (pinfunction "2_2") (pintype "passive"))
      (node (ref "R33") (pin "2") (pinfunction "2_2") (pintype "passive"))
      (node (ref "R34") (pin "2") (pinfunction "2_2") (pintype "passive"))
      (node (ref "R35") (pin "2") (pinfunction "2_2") (pintype "passive"))
      (node (ref "R36") (pin "2") (pinfunction "2_2") (pintype "passive"))
      (node (ref "R37") (pin "2") (pinfunction "2_2") (pintype "passive"))
      (node (ref "R38") (pin "2") (pinfunction "2_2") (pintype "passive"))
      (node (ref "R39") (pin "2") (pinfunction "2_2") (pintype "passive"))
      (node (ref "R5") (pin "2") (pinfunction "2_2") (pintype "passive"))
      (node (ref "T1") (pin "10") (pinfunction "F3_10") (pintype "passive"))
      (node (ref "T2") (pin "9") (pinfunction "F4_9") (pintype "passive"))
      (node (ref "T202") (pin "C") (pinfunction "C_C") (pintype "passive"))
      (node (ref "TP1") (pin "GND") (pinfunction "GND1_GND") (pintype "power_in"))
      (node (ref "TP10") (pin "GND") (pinfunction "GND1_GND") (pintype "power_in"))
      (node (ref "TP11") (pin "GND") (pinfunction "GND1_GND") (pintype "power_in"))
      (node (ref "TP12") (pin "GND") (pinfunction "GND1_GND") (pintype "power_in"))
      (node (ref "TP13") (pin "GND") (pinfunction "GND1_GND") (pintype "power_in"))
      (node (ref "TP14") (pin "GND") (pinfunction "GND1_GND") (pintype "power_in"))
      (node (ref "TP15") (pin "GND") (pinfunction "GND1_GND") (pintype "power_in"))
      (node (ref "TP16") (pin "GND") (pinfunction "GND1_GND") (pintype "power_in"))
      (node (ref "TP17") (pin "GND") (pinfunction "GND1_GND") (pintype "power_in"))
      (node (ref "TP18") (pin "GND") (pinfunction "GND1_GND") (pintype "power_in"))
      (node (ref "TP19") (pin "GND") (pinfunction "GND1_GND") (pintype "power_in"))
      (node (ref "TP2") (pin "GND") (pinfunction "GND1_GND") (pintype "power_in"))
      (node (ref "TP3") (pin "GND") (pinfunction "GND1_GND") (pintype "power_in"))
      (node (ref "TP4") (pin "GND") (pinfunction "GND1_GND") (pintype "power_in"))
      (node (ref "TP5") (pin "GND") (pinfunction "GND1_GND") (pintype "power_in"))
      (node (ref "TP6") (pin "GND") (pinfunction "GND1_GND") (pintype "power_in"))
      (node (ref "TP7") (pin "GND") (pinfunction "GND1_GND") (pintype "power_in"))
      (node (ref "TP8") (pin "GND") (pinfunction "GND1_GND") (pintype "power_in"))
      (node (ref "TP9") (pin "GND") (pinfunction "GND1_GND") (pintype "power_in"))
      (node (ref "X1") (pin "2") (pinfunction "KL_2") (pintype "passive"))
      (node (ref "X101") (pin "P1") (pinfunction "P$1_P1") (pintype "bidirectional"))
      (node (ref "X101") (pin "P2") (pinfunction "P$2_P2") (pintype "bidirectional"))
    )
    (net (code "29") (name "Net-(C1-Pad1)") (class "Default")
      (node (ref "C1") (pin "1") (pinfunction "1_1") (pintype "passive"))
      (node (ref "R1") (pin "2") (pinfunction "2_2") (pintype "passive"))
      (node (ref "R7") (pin "2") (pinfunction "2_2") (pintype "passive"))
    )
    (net (code "30") (name "Net-(C3-Pad1)") (class "Default")
      (node (ref "C3") (pin "1") (pinfunction "1_1") (pintype "passive"))
      (node (ref "R10") (pin "2") (pinfunction "2_2") (pintype "passive"))
    )
    (net (code "31") (name "Net-(C4-Pad1)") (class "Default")
      (node (ref "C4") (pin "1") (pinfunction "1_1") (pintype "passive"))
      (node (ref "R9") (pin "2") (pinfunction "2_2") (pintype "passive"))
    )
    (net (code "32") (name "Net-(C6-Pad1)") (class "Default")
      (node (ref "C6") (pin "1") (pinfunction "1_1") (pintype "passive"))
      (node (ref "R12") (pin "2") (pinfunction "2_2") (pintype "passive"))
      (node (ref "R4") (pin "1") (pinfunction "1_1") (pintype "passive"))
    )
    (net (code "33") (name "Net-(C7-Pad1)") (class "Default")
      (node (ref "C7") (pin "1") (pinfunction "1_1") (pintype "passive"))
      (node (ref "R14") (pin "2") (pinfunction "2_2") (pintype "passive"))
      (node (ref "R20") (pin "2") (pinfunction "2_2") (pintype "passive"))
    )
    (net (code "34") (name "Net-(C9-Pad1)") (class "Default")
      (node (ref "C9") (pin "1") (pinfunction "1_1") (pintype "passive"))
      (node (ref "R23") (pin "2") (pinfunction "2_2") (pintype "passive"))
    )
    (net (code "35") (name "Net-(C10-Pad1)") (class "Default")
      (node (ref "C10") (pin "1") (pinfunction "1_1") (pintype "passive"))
      (node (ref "R22") (pin "2") (pinfunction "2_2") (pintype "passive"))
    )
    (net (code "36") (name "Net-(C12-Pad1)") (class "Default")
      (node (ref "C12") (pin "1") (pinfunction "1_1") (pintype "passive"))
      (node (ref "R17") (pin "1") (pinfunction "1_1") (pintype "passive"))
      (node (ref "R25") (pin "2") (pinfunction "2_2") (pintype "passive"))
    )
    (net (code "37") (name "Net-(C13-Pad1)") (class "Default")
      (node (ref "C13") (pin "1") (pinfunction "1_1") (pintype "passive"))
      (node (ref "IC301") (pin "IN") (pinfunction "IN_IN") (pintype "input"))
      (node (ref "R302") (pin "2") (pinfunction "2_2") (pintype "passive"))
    )
    (net (code "38") (name "Net-(C23-Pad1)") (class "Default")
      (node (ref "C23") (pin "1") (pinfunction "1_1") (pintype "passive"))
      (node (ref "C301") (pin "+") (pinfunction "+_+") (pintype "passive"))
      (node (ref "D2") (pin "C") (pinfunction "C_C") (pintype "passive"))
      (node (ref "L4") (pin "1") (pinfunction "1_1") (pintype "passive"))
      (node (ref "R301") (pin "2") (pinfunction "2_2") (pintype "passive"))
    )
    (net (code "39") (name "Net-(C30-Pad1)") (class "Default")
      (node (ref "C30") (pin "1") (pinfunction "1_1") (pintype "passive"))
      (node (ref "IC302") (pin "IN") (pinfunction "IN_IN") (pintype "input"))
      (node (ref "R303") (pin "2") (pinfunction "2_2") (pintype "passive"))
    )
    (net (code "40") (name "Net-(C102-Pad1)") (class "Default")
      (node (ref "C102") (pin "1") (pinfunction "1_1") (pintype "passive"))
      (node (ref "R107") (pin "2") (pinfunction "2_2") (pintype "passive"))
      (node (ref "R108") (pin "1") (pinfunction "1_1") (pintype "passive"))
    )
    (net (code "41") (name "Net-(C104-Pad1)") (class "Default")
      (node (ref "C104") (pin "1") (pinfunction "1_1") (pintype "passive"))
      (node (ref "R109") (pin "2") (pinfunction "2_2") (pintype "passive"))
      (node (ref "R110") (pin "1") (pinfunction "1_1") (pintype "passive"))
    )
    (net (code "42") (name "Net-(C106-Pad1)") (class "Default")
      (node (ref "C106") (pin "1") (pinfunction "1_1") (pintype "passive"))
      (node (ref "R111") (pin "2") (pinfunction "2_2") (pintype "passive"))
    )
    (net (code "43") (name "Net-(C107-Pad1)") (class "Default")
      (node (ref "C107") (pin "1") (pinfunction "1_1") (pintype "passive"))
      (node (ref "R112") (pin "2") (pinfunction "2_2") (pintype "passive"))
    )
    (net (code "44") (name "Net-(C109-Pad1)") (class "Default")
      (node (ref "C109") (pin "1") (pinfunction "1_1") (pintype "passive"))
      (node (ref "R115") (pin "2") (pinfunction "2_2") (pintype "passive"))
    )
    (net (code "45") (name "Net-(C110-Pad1)") (class "Default")
      (node (ref "C110") (pin "1") (pinfunction "1_1") (pintype "passive"))
      (node (ref "R116") (pin "2") (pinfunction "2_2") (pintype "passive"))
    )
    (net (code "46") (name "Net-(C111-Pad1)") (class "Default")
      (node (ref "C111") (pin "1") (pinfunction "1_1") (pintype "passive"))
      (node (ref "R117") (pin "2") (pinfunction "2_2") (pintype "passive"))
      (node (ref "R118") (pin "2") (pinfunction "2_2") (pintype "passive"))
    )
    (net (code "47") (name "Net-(C112-Pad1)") (class "Default")
      (node (ref "C112") (pin "1") (pinfunction "1_1") (pintype "passive"))
      (node (ref "R119") (pin "2") (pinfunction "2_2") (pintype "passive"))
      (node (ref "R120") (pin "2") (pinfunction "2_2") (pintype "passive"))
    )
    (net (code "48") (name "Net-(C207-Pad1)") (class "Default")
      (node (ref "C207") (pin "1") (pinfunction "1_1") (pintype "passive"))
      (node (ref "R214") (pin "1") (pinfunction "1_1") (pintype "passive"))
    )
    (net (code "49") (name "Net-(C209-Pad1)") (class "Default")
      (node (ref "C209") (pin "1") (pinfunction "1_1") (pintype "passive"))
      (node (ref "R216") (pin "2") (pinfunction "2_2") (pintype "passive"))
    )
    (net (code "50") (name "Net-(C303-Pad1)") (class "Default")
      (node (ref "C303") (pin "1") (pinfunction "1_1") (pintype "passive"))
      (node (ref "L4") (pin "2") (pinfunction "2_2") (pintype "passive"))
      (node (ref "L5") (pin "1") (pinfunction "1_1") (pintype "passive"))
      (node (ref "R40") (pin "1") (pinfunction "1_1") (pintype "passive"))
      (node (ref "R43") (pin "1") (pinfunction "1_1") (pintype "passive"))
    )
    (net (code "51") (name "Net-(D2-PadA)") (class "Default")
      (node (ref "D2") (pin "A") (pinfunction "A_A") (pintype "passive"))
      (node (ref "R302") (pin "1") (pinfunction "1_1") (pintype "passive"))
      (node (ref "R303") (pin "1") (pinfunction "1_1") (pintype "passive"))
    )
    (net (code "52") (name "Net-(D301-PadC)") (class "Default")
      (node (ref "D301") (pin "C") (pinfunction "C_C") (pintype "passive"))
      (node (ref "J1") (pin "2") (pinfunction "2_2") (pintype "passive"))
      (node (ref "R301") (pin "1") (pinfunction "1_1") (pintype "passive"))
    )
    (net (code "53") (name "Net-(IC201A-I)") (class "Default")
      (node (ref "IC201") (pin "2") (pinfunction "I_2") (pintype "input"))
      (node (ref "R204") (pin "1") (pinfunction "1_1") (pintype "passive"))
      (node (ref "R42") (pin "2") (pinfunction "2_2") (pintype "passive"))
    )
    (net (code "54") (name "Net-(IC201A-O)") (class "Default")
      (node (ref "IC201") (pin "4") (pinfunction "O_4") (pintype "output"))
      (node (ref "Q201") (pin "1") (pinfunction "G_1") (pintype "passive"))
      (node (ref "R41") (pin "2") (pinfunction "2_2") (pintype "passive"))
    )
    (net (code "55") (name "Net-(IC202A-+IN)") (class "Default")
      (node (ref "C208") (pin "1") (pinfunction "1_1") (pintype "passive"))
      (node (ref "IC202") (pin "3") (pinfunction "+IN_3") (pintype "input"))
      (node (ref "R209") (pin "2") (pinfunction "2_2") (pintype "passive"))
      (node (ref "R211") (pin "1") (pinfunction "1_1") (pintype "passive"))
    )
    (net (code "56") (name "Net-(IC202A--IN)") (class "Default")
      (node (ref "C209") (pin "2") (pinfunction "2_2") (pintype "passive"))
      (node (ref "IC202") (pin "2") (pinfunction "-IN_2") (pintype "input"))
      (node (ref "R212") (pin "2") (pinfunction "2_2") (pintype "passive"))
      (node (ref "R214") (pin "2") (pinfunction "2_2") (pintype "passive"))
      (node (ref "R219") (pin "1") (pinfunction "1_1") (pintype "passive"))
    )
    (net (code "57") (name "Net-(IC202A-OUT)") (class "Default")
      (node (ref "IC202") (pin "1") (pinfunction "OUT_1") (pintype "output"))
      (node (ref "R216") (pin "1") (pinfunction "1_1") (pintype "passive"))
      (node (ref "R217") (pin "1") (pinfunction "1_1") (pintype "passive"))
    )
    (net (code "58") (name "Net-(IC202B-+IN)") (class "Default")
      (node (ref "IC202") (pin "5") (pinfunction "+IN_5") (pintype "input"))
      (node (ref "Q201") (pin "3") (pinfunction "D_3") (pintype "passive"))
      (node (ref "R207") (pin "2") (pinfunction "2_2") (pintype "passive"))
    )
    (net (code "59") (name "Net-(IC202B--IN)") (class "Default")
      (node (ref "IC202") (pin "6") (pinfunction "-IN_6") (pintype "input"))
      (node (ref "IC202") (pin "7") (pinfunction "OUT_7") (pintype "output"))
      (node (ref "R209") (pin "1") (pinfunction "1_1") (pintype "passive"))
      (node (ref "TP12") (pin "TP") (pinfunction "1_TP") (pintype "passive"))
    )
    (net (code "60") (name "Net-(IC202C-+IN)") (class "Default")
      (node (ref "IC202") (pin "10") (pinfunction "+IN_10") (pintype "input"))
      (node (ref "R203") (pin "2") (pinfunction "2_2") (pintype "passive"))
      (node (ref "R206") (pin "1") (pinfunction "1_1") (pintype "passive"))
    )
    (net (code "61") (name "Net-(IC202C--IN)") (class "Default")
      (node (ref "IC202") (pin "9") (pinfunction "-IN_9") (pintype "input"))
      (node (ref "JP202") (pin "1") (pinfunction "1_1") (pintype "passive"))
      (node (ref "R202") (pin "2") (pinfunction "2_2") (pintype "passive"))
      (node (ref "R205") (pin "1") (pinfunction "1_1") (pintype "passive"))
    )
    (net (code "62") (name "Net-(IC202C-OUT)") (class "Default")
      (node (ref "IC202") (pin "8") (pinfunction "OUT_8") (pintype "output"))
      (node (ref "JP202") (pin "2") (pinfunction "2_2") (pintype "passive"))
      (node (ref "R205") (pin "2") (pinfunction "2_2") (pintype "passive"))
      (node (ref "R207") (pin "1") (pinfunction "1_1") (pintype "passive"))
    )
    (net (code "63") (name "Net-(IC202D-+IN)") (class "Default")
      (node (ref "C201") (pin "1") (pinfunction "1_1") (pintype "passive"))
      (node (ref "IC202") (pin "12") (pinfunction "+IN_12") (pintype "input"))
      (node (ref "R201") (pin "2") (pinfunction "S_2") (pintype "passive"))
    )
    (net (code "64") (name "Net-(IC202D--IN)") (class "Default")
      (node (ref "IC202") (pin "13") (pinfunction "-IN_13") (pintype "input"))
      (node (ref "IC202") (pin "14") (pinfunction "OUT_14") (pintype "output"))
      (node (ref "R206") (pin "2") (pinfunction "2_2") (pintype "passive"))
      (node (ref "TP13") (pin "TP") (pinfunction "1_TP") (pintype "passive"))
    )
    (net (code "65") (name "Net-(J2-Pad3)") (class "Default")
      (node (ref "J2") (pin "3") (pinfunction "3_3") (pintype "passive"))
      (node (ref "R29") (pin "2") (pinfunction "2_2") (pintype "passive"))
    )
    (net (code "66") (name "Net-(J101-1)") (class "Default")
      (node (ref "C24") (pin "2") (pinfunction "2_2") (pintype "passive"))
      (node (ref "C25") (pin "2") (pinfunction "2_2") (pintype "passive"))
      (node (ref "C28") (pin "2") (pinfunction "2_2") (pintype "passive"))
      (node (ref "J101") (pin "C") (pinfunction "1_C") (pintype "passive"))
    )
    (net (code "67") (name "Net-(J102-1)") (class "Default")
      (node (ref "C26") (pin "2") (pinfunction "2_2") (pintype "passive"))
      (node (ref "C27") (pin "2") (pinfunction "2_2") (pintype "passive"))
      (node (ref "C29") (pin "2") (pinfunction "2_2") (pintype "passive"))
      (node (ref "J102") (pin "C") (pinfunction "1_C") (pintype "passive"))
    )
    (net (code "68") (name "Net-(J201-1)") (class "Default")
      (node (ref "J201") (pin "C") (pinfunction "1_C") (pintype "passive"))
      (node (ref "JP201") (pin "2") (pinfunction "2_2") (pintype "passive"))
      (node (ref "R202") (pin "1") (pinfunction "1_1") (pintype "passive"))
    )
    (net (code "69") (name "Net-(J201-GND1-PadG1)") (class "Default")
      (node (ref "J201") (pin "G1") (pinfunction "GND1_G1") (pintype "power_in"))
      (node (ref "J201") (pin "G2") (pinfunction "GND1_G2") (pintype "power_in"))
      (node (ref "J201") (pin "G3") (pinfunction "GND1_G3") (pintype "power_in"))
      (node (ref "J201") (pin "G4") (pinfunction "GND1_G4") (pintype "power_in"))
      (node (ref "JP201") (pin "1") (pinfunction "1_1") (pintype "passive"))
      (node (ref "R203") (pin "1") (pinfunction "1_1") (pintype "passive"))
    )
    (net (code "70") (name "Net-(J202-1)") (class "Default")
      (node (ref "J202") (pin "C") (pinfunction "1_C") (pintype "passive"))
      (node (ref "R42") (pin "1") (pinfunction "1_1") (pintype "passive"))
    )
    (net (code "71") (name "Net-(LED1-C)") (class "Default")
      (node (ref "LED1") (pin "K") (pinfunction "C_K") (pintype "passive"))
      (node (ref "R28") (pin "1") (pinfunction "1_1") (pintype "passive"))
    )
    (net (code "72") (name "Net-(LED2-C)") (class "Default")
      (node (ref "LED2") (pin "K") (pinfunction "C_K") (pintype "passive"))
      (node (ref "R27") (pin "1") (pinfunction "1_1") (pintype "passive"))
    )
    (net (code "73") (name "Net-(LED3-C)") (class "Default")
      (node (ref "LED3") (pin "K") (pinfunction "C_K") (pintype "passive"))
      (node (ref "R41") (pin "1") (pinfunction "1_1") (pintype "passive"))
    )
    (net (code "74") (name "Net-(R217-Pad2)") (class "Default")
      (node (ref "R217") (pin "2") (pinfunction "2_2") (pintype "passive"))
      (node (ref "R218") (pin "1") (pinfunction "1_1") (pintype "passive"))
      (node (ref "T201") (pin "B") (pinfunction "B_B") (pintype "passive"))
      (node (ref "T202") (pin "B") (pinfunction "B_B") (pintype "passive"))
    )
    (net (code "75") (name "Net-(T1-F1)") (class "Default")
      (node (ref "R31") (pin "1") (pinfunction "1_1") (pintype "passive"))
      (node (ref "T1") (pin "12") (pinfunction "F1_12") (pintype "passive"))
      (node (ref "T1") (pin "2") (pinfunction "S2_2") (pintype "passive"))
    )
    (net (code "76") (name "Net-(T1-F4)") (class "Default")
      (node (ref "T1") (pin "3") (pinfunction "S3_3") (pintype "passive"))
      (node (ref "T1") (pin "9") (pinfunction "F4_9") (pintype "passive"))
    )
    (net (code "77") (name "Net-(T1-F5)") (class "Default")
      (node (ref "C28") (pin "1") (pinfunction "1_1") (pintype "passive"))
      (node (ref "T1") (pin "4") (pinfunction "S4_4") (pintype "passive"))
      (node (ref "T1") (pin "8") (pinfunction "F5_8") (pintype "passive"))
    )
    (net (code "78") (name "Net-(T1-F6)") (class "Default")
      (node (ref "C24") (pin "1") (pinfunction "1_1") (pintype "passive"))
      (node (ref "T1") (pin "5") (pinfunction "S5_5") (pintype "passive"))
      (node (ref "T1") (pin "7") (pinfunction "F6_7") (pintype "passive"))
    )
    (net (code "79") (name "Net-(T1-S6)") (class "Default")
      (node (ref "C25") (pin "1") (pinfunction "1_1") (pintype "passive"))
      (node (ref "T1") (pin "6") (pinfunction "S6_6") (pintype "passive"))
    )
    (net (code "80") (name "Net-(T2-F1)") (class "Default")
      (node (ref "C27") (pin "1") (pinfunction "1_1") (pintype "passive"))
      (node (ref "T2") (pin "12") (pinfunction "F1_12") (pintype "passive"))
      (node (ref "T2") (pin "2") (pinfunction "S2_2") (pintype "passive"))
    )
    (net (code "81") (name "Net-(T2-F2)") (class "Default")
      (node (ref "C29") (pin "1") (pinfunction "1_1") (pintype "passive"))
      (node (ref "T2") (pin "11") (pinfunction "F2_11") (pintype "passive"))
      (node (ref "T2") (pin "3") (pinfunction "S3_3") (pintype "passive"))
    )
    (net (code "82") (name "Net-(T2-F3)") (class "Default")
      (node (ref "T2") (pin "10") (pinfunction "F3_10") (pintype "passive"))
      (node (ref "T2") (pin "4") (pinfunction "S4_4") (pintype "passive"))
    )
    (net (code "83") (name "Net-(T2-F6)") (class "Default")
      (node (ref "R30") (pin "2") (pinfunction "2_2") (pintype "passive"))
      (node (ref "T2") (pin "5") (pinfunction "S5_5") (pintype "passive"))
      (node (ref "T2") (pin "7") (pinfunction "F6_7") (pintype "passive"))
    )
    (net (code "84") (name "Net-(T2-S1)") (class "Default")
      (node (ref "C26") (pin "1") (pinfunction "1_1") (pintype "passive"))
      (node (ref "T2") (pin "1") (pinfunction "S1_1") (pintype "passive"))
    )
    (net (code "85") (name "Net-(X1A-KL)") (class "Default")
      (node (ref "J1") (pin "1") (pinfunction "1_1") (pintype "passive"))
      (node (ref "X1") (pin "1") (pinfunction "KL_1") (pintype "passive"))
    )
    (net (code "86") (name "VB") (class "Default")
      (node (ref "C17") (pin "1") (pinfunction "1_1") (pintype "passive"))
      (node (ref "C18") (pin "1") (pinfunction "1_1") (pintype "passive"))
      (node (ref "C19") (pin "1") (pinfunction "1_1") (pintype "passive"))
      (node (ref "C20") (pin "1") (pinfunction "1_1") (pintype "passive"))
      (node (ref "C21") (pin "1") (pinfunction "1_1") (pintype "passive"))
      (node (ref "C304") (pin "1") (pinfunction "1_1") (pintype "passive"))
      (node (ref "L5") (pin "2") (pinfunction "2_2") (pintype "passive"))
      (node (ref "L6") (pin "2") (pinfunction "2_2") (pintype "passive"))
      (node (ref "L7") (pin "2") (pinfunction "2_2") (pintype "passive"))
      (node (ref "R30") (pin "1") (pinfunction "1_1") (pintype "passive"))
      (node (ref "R40") (pin "2") (pinfunction "2_2") (pintype "passive"))
      (node (ref "R43") (pin "2") (pinfunction "2_2") (pintype "passive"))
    )
    (net (code "87") (name "unconnected-(J2-Pad4)") (class "Default")
      (node (ref "J2") (pin "4") (pinfunction "4_4") (pintype "passive"))
    )
  )
)
